# rev_o_v26.net
KiCad netlist of a schematic drawn in EAGLE
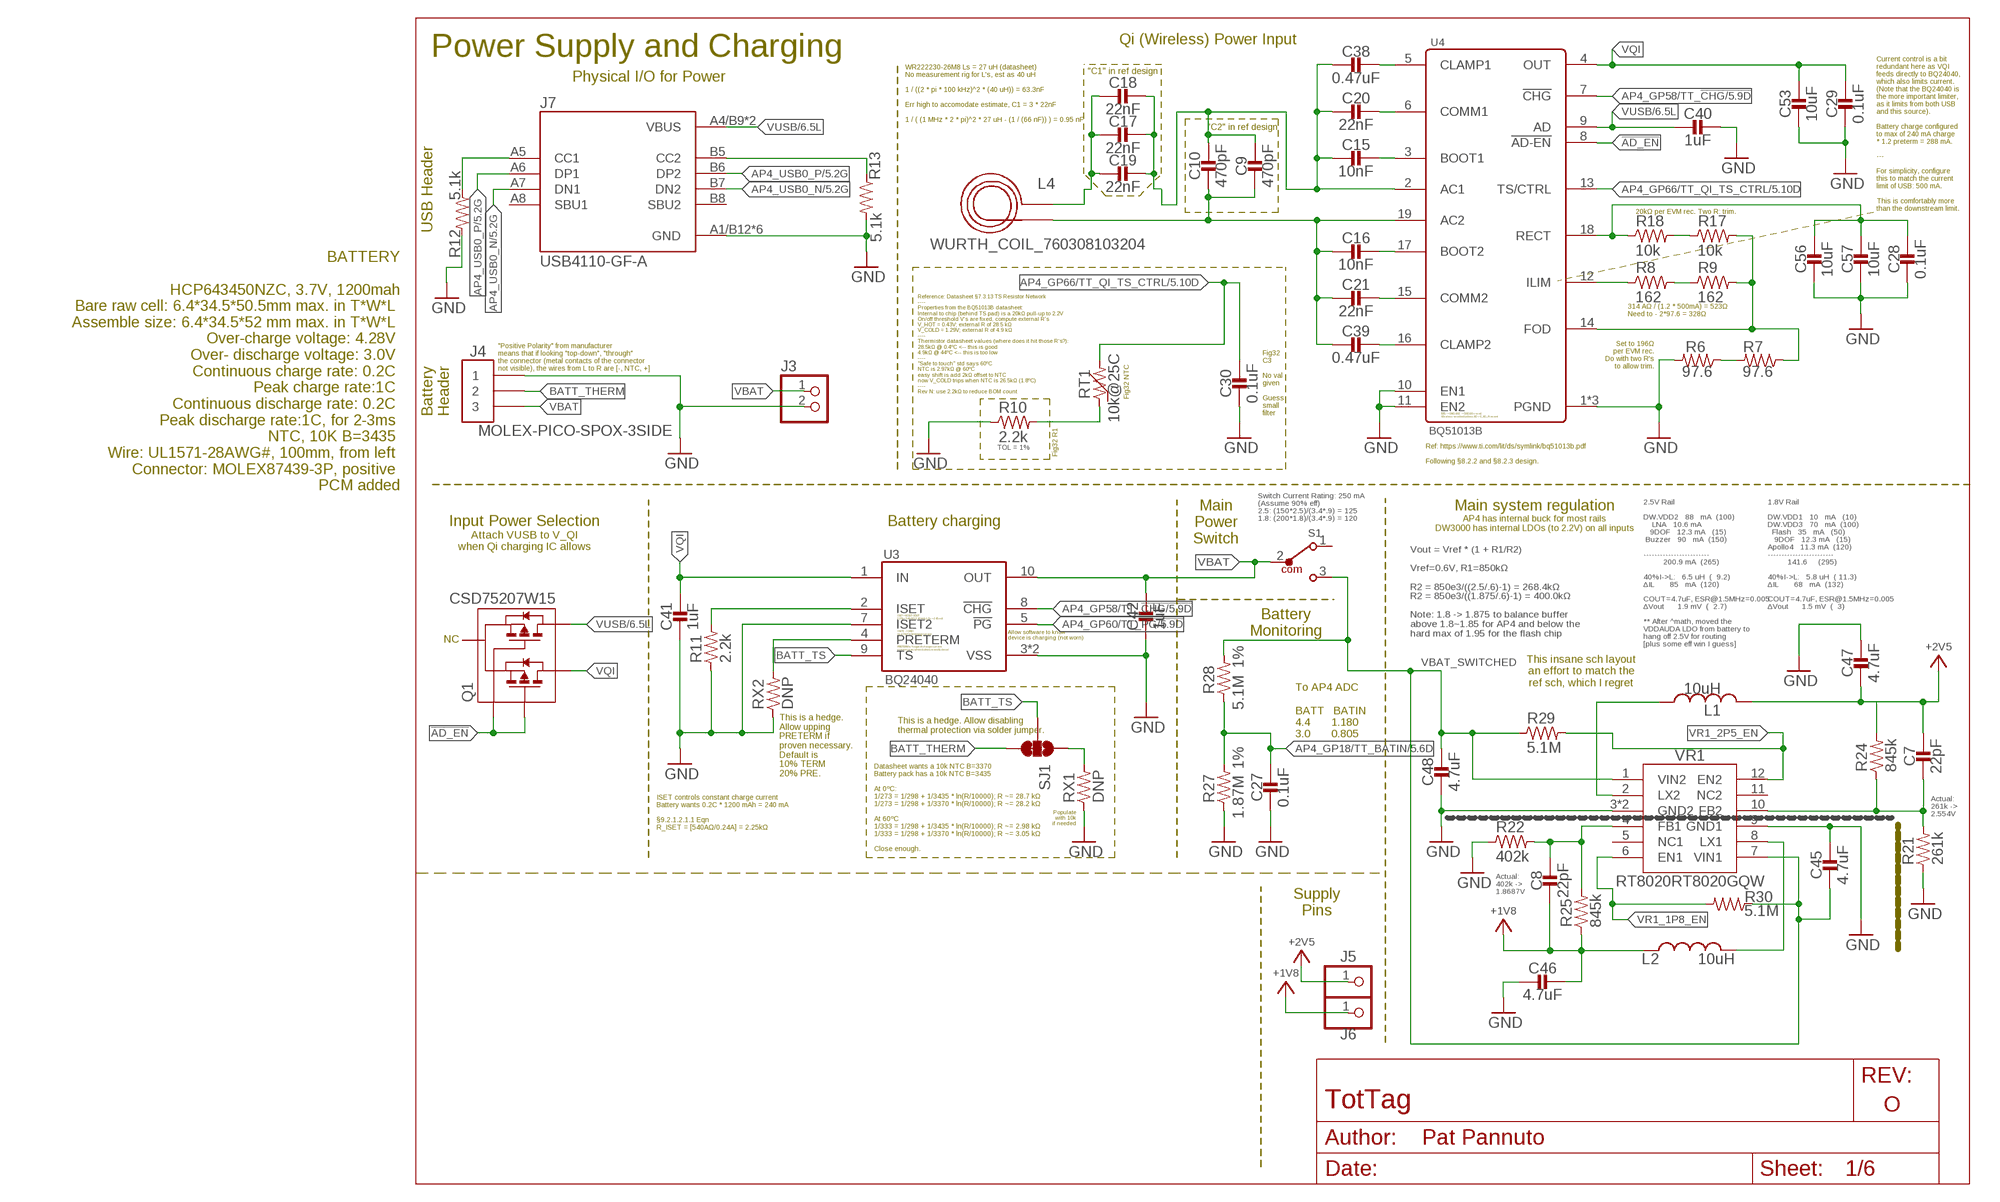
[diagram p0: schematic, sheet 1]
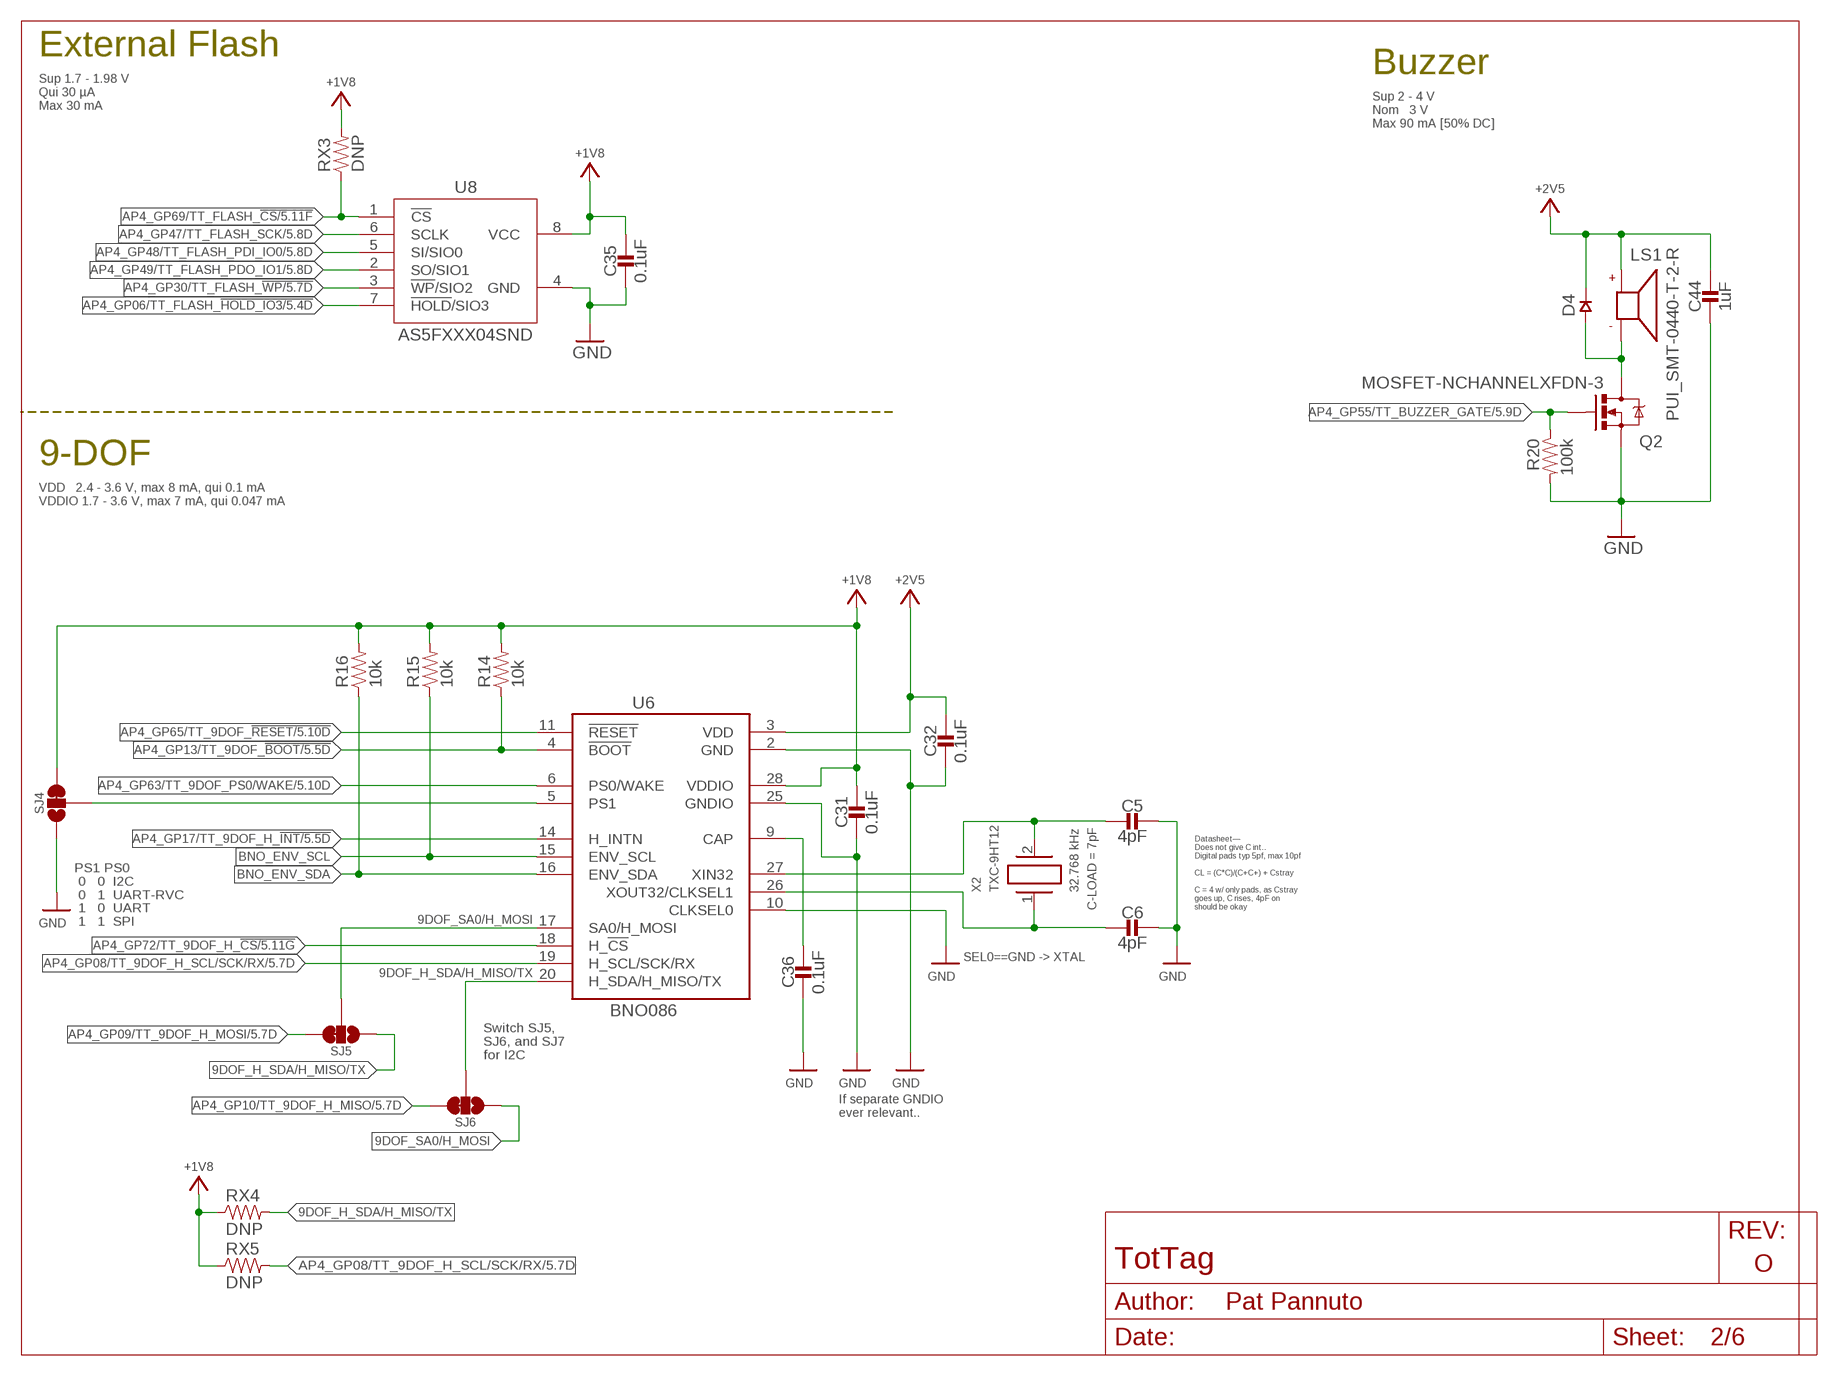
[diagram p1: schematic, sheet 2]
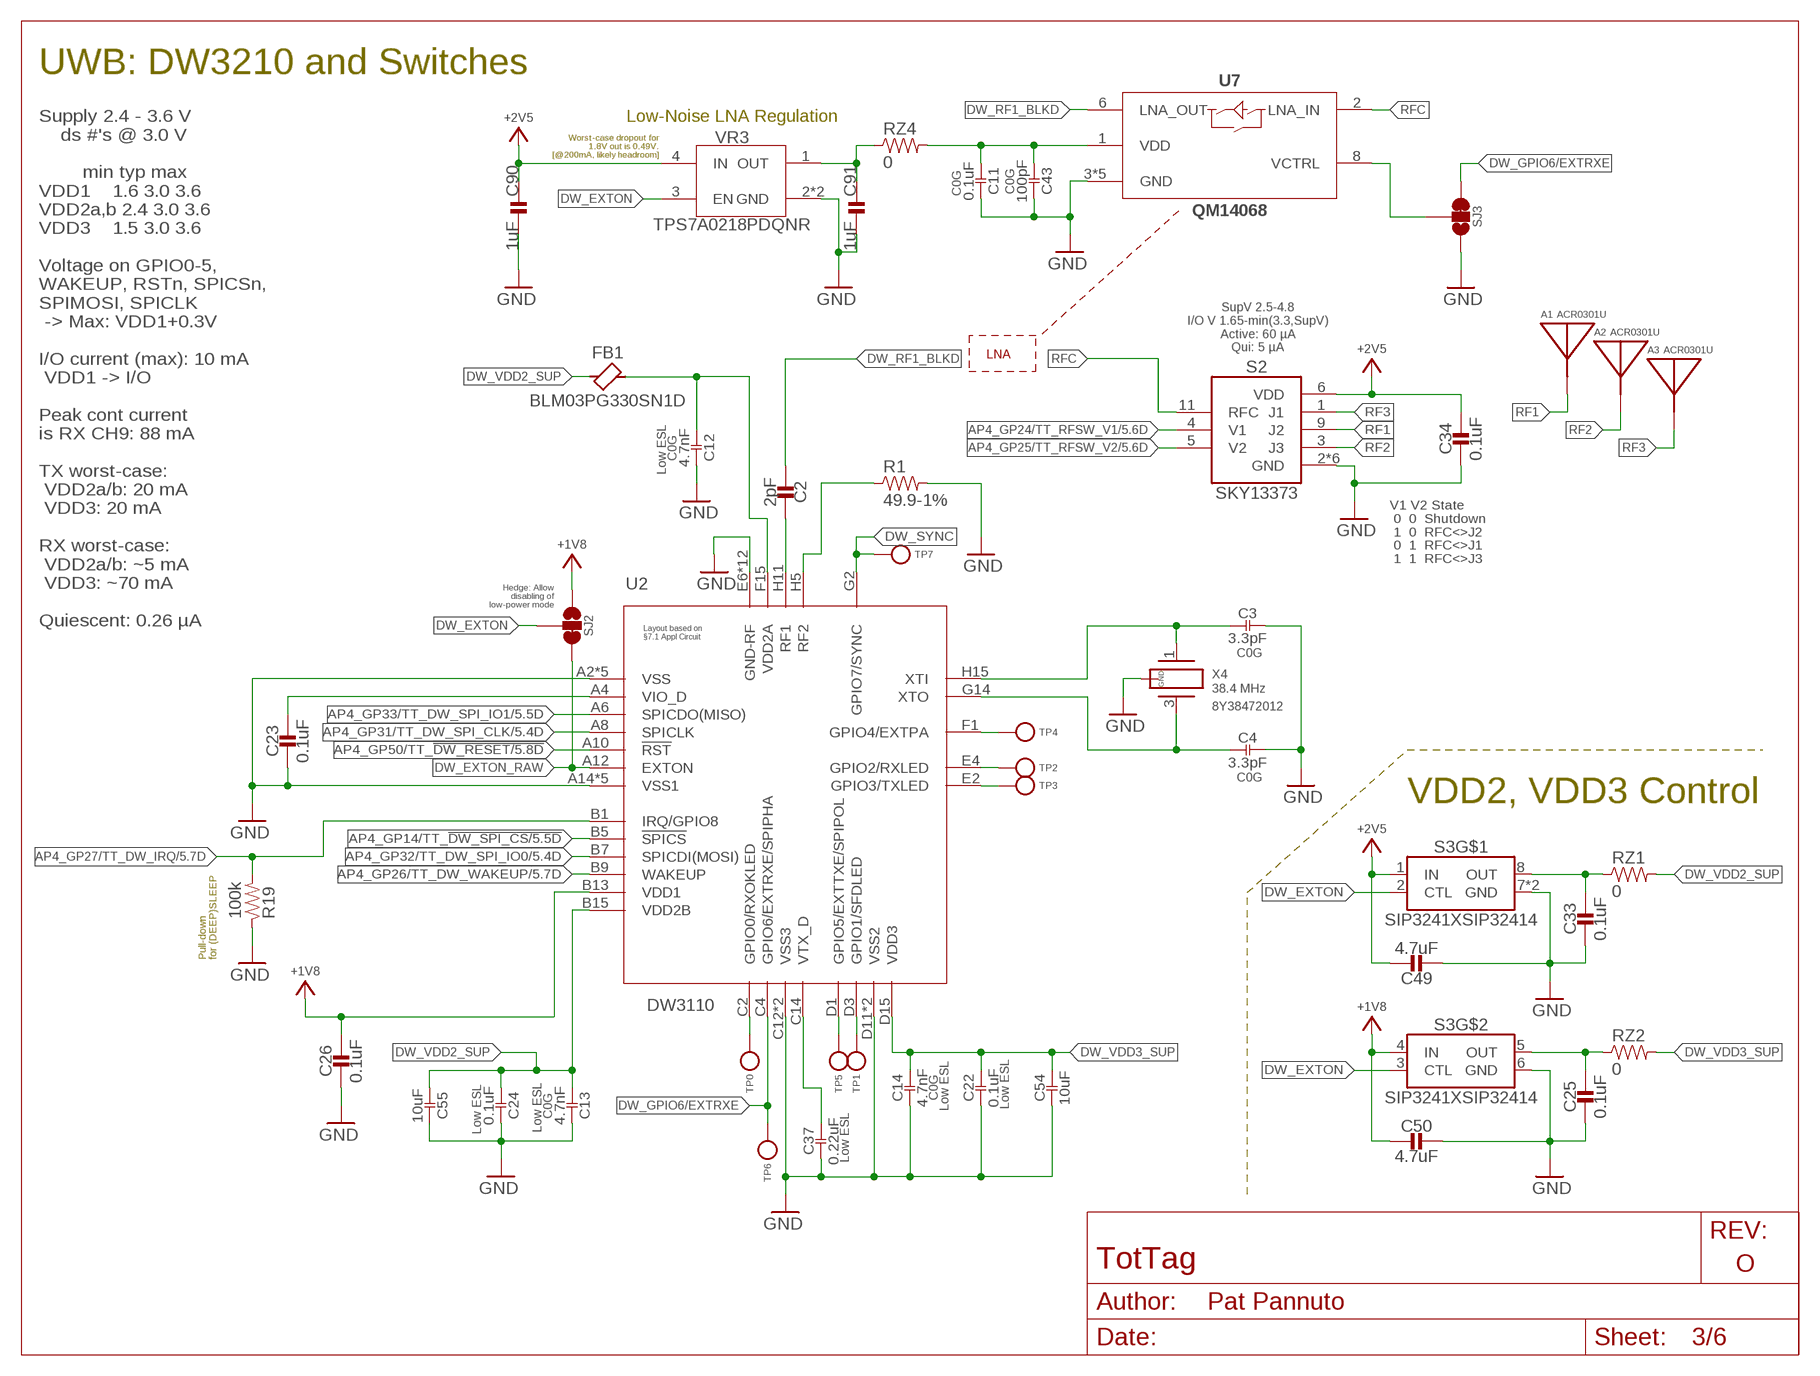
[diagram p2: schematic, sheet 3]
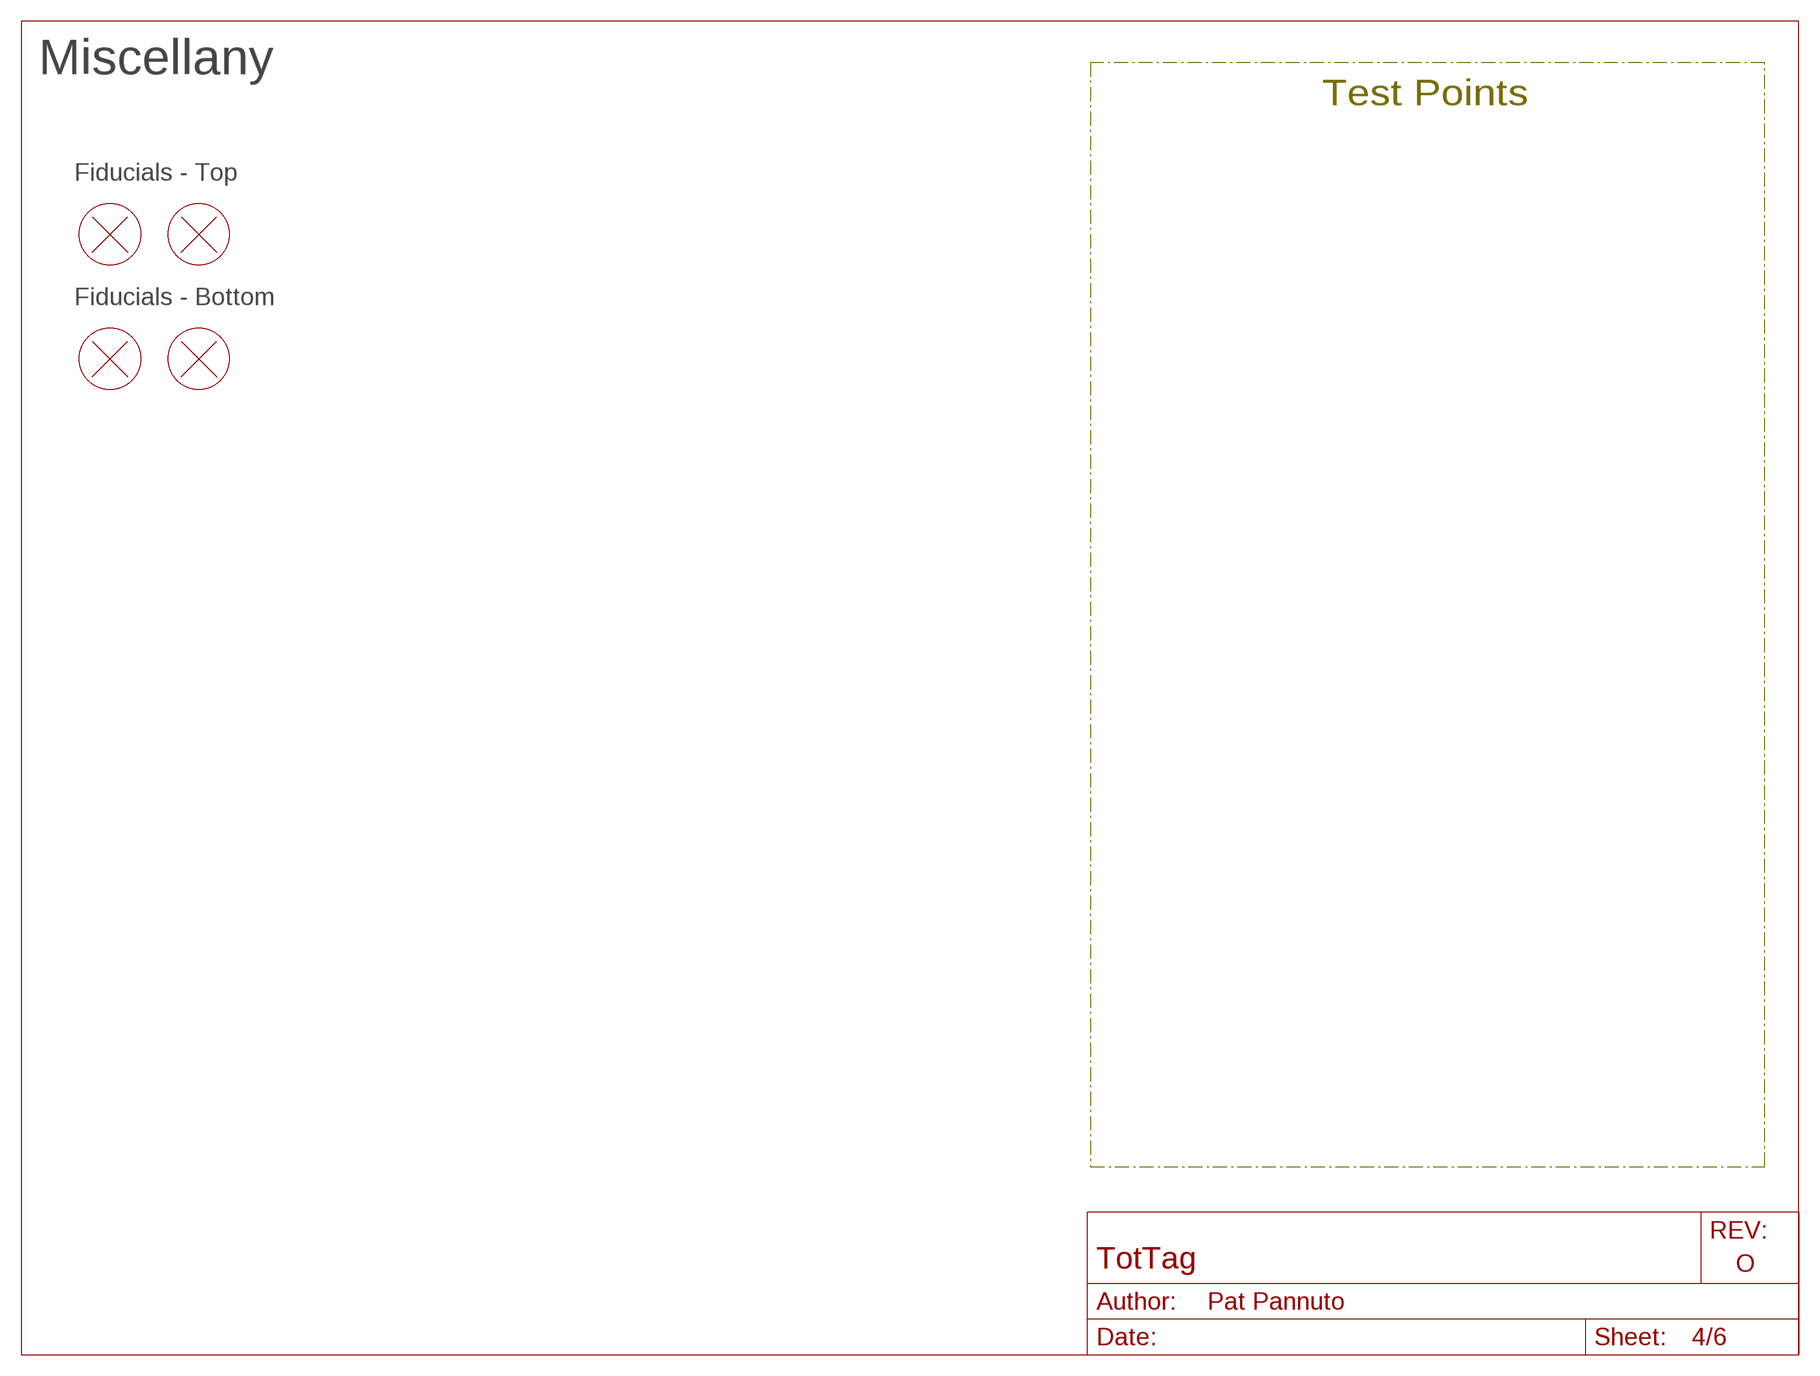
[diagram p3: schematic, sheet 4]
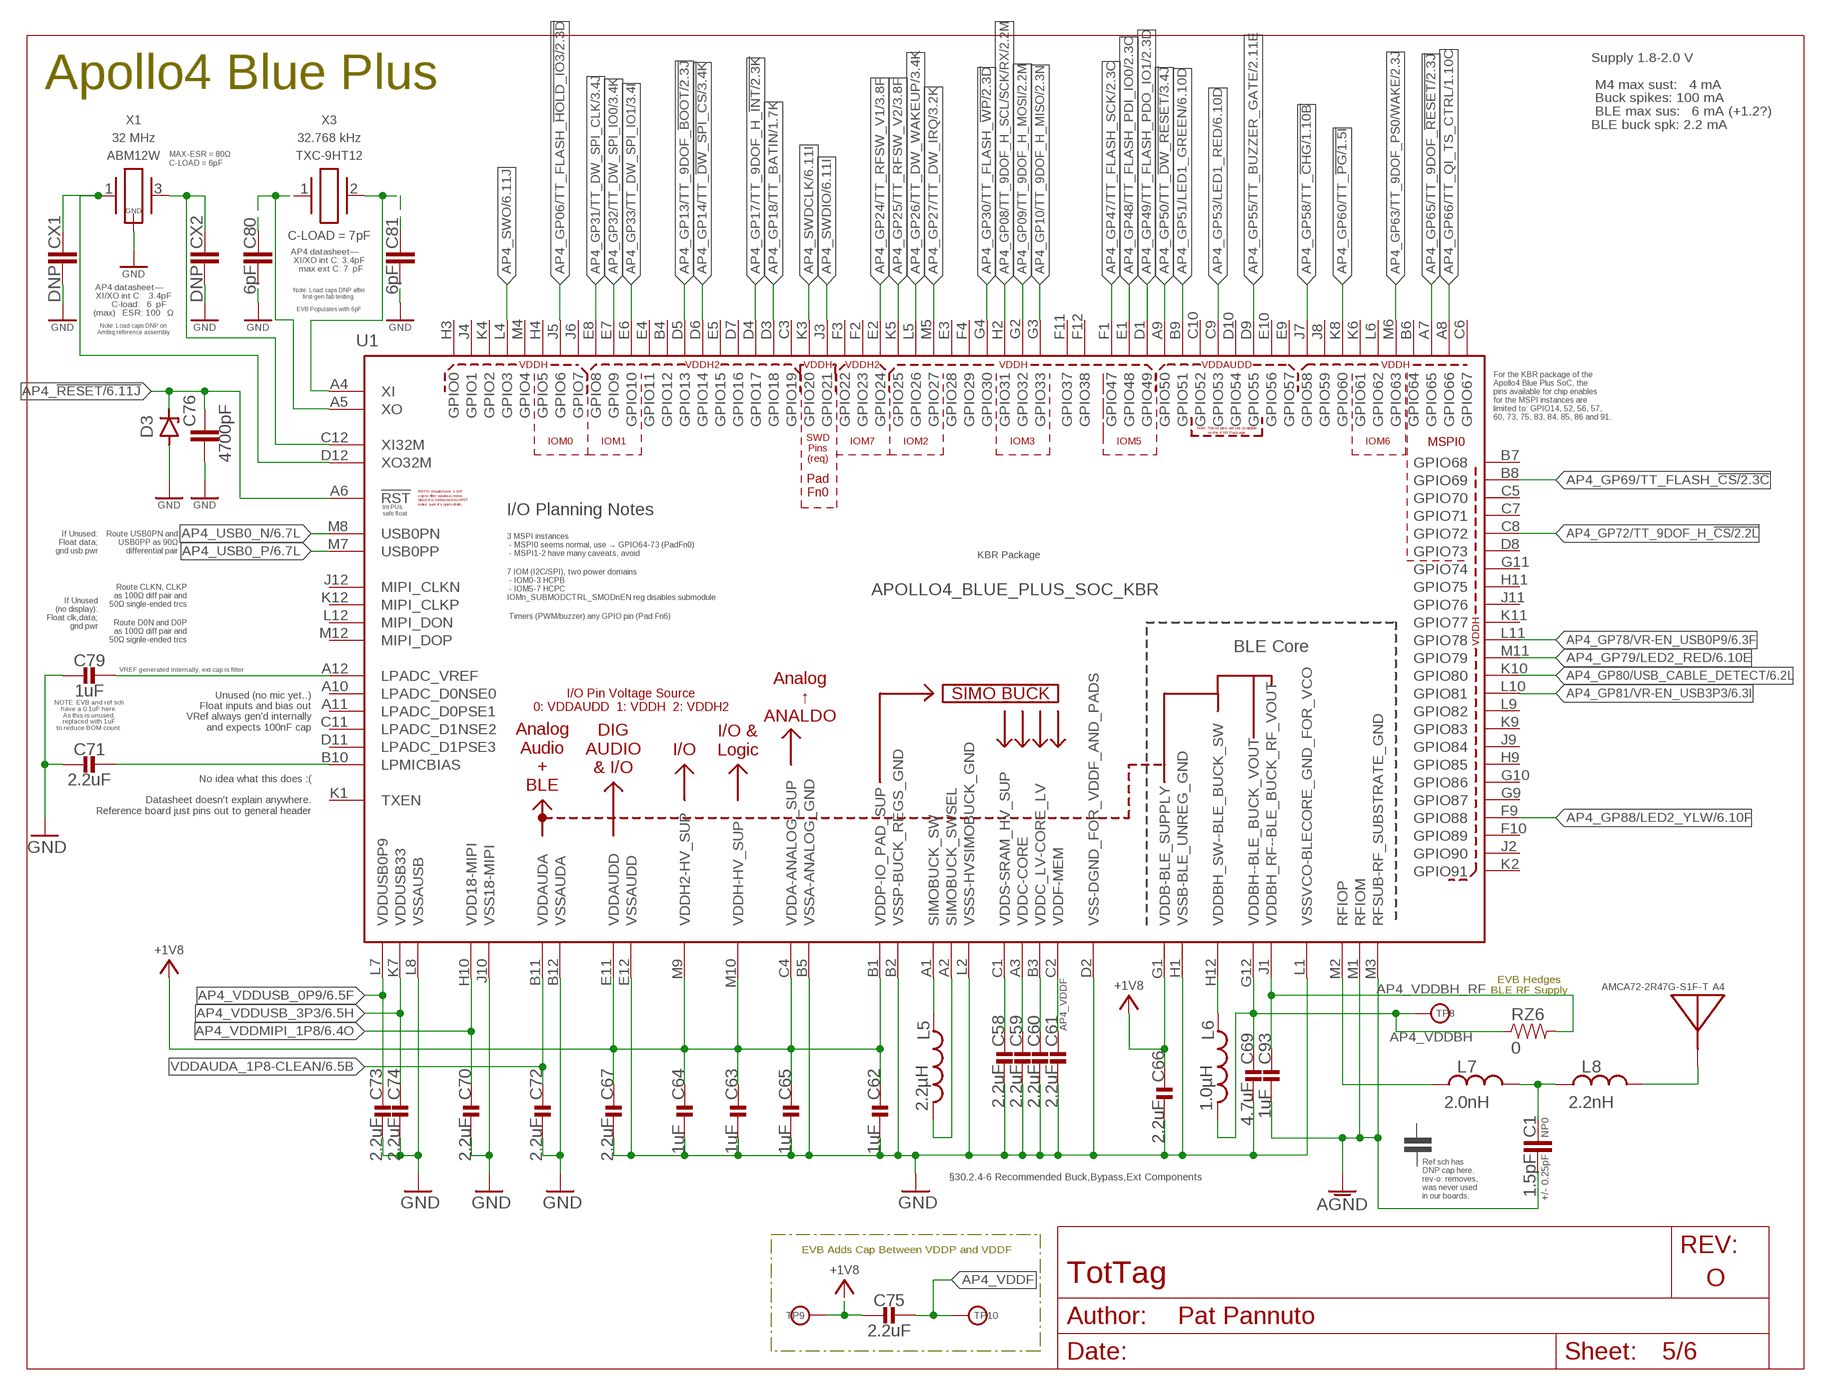
[diagram p4: schematic, sheet 5]
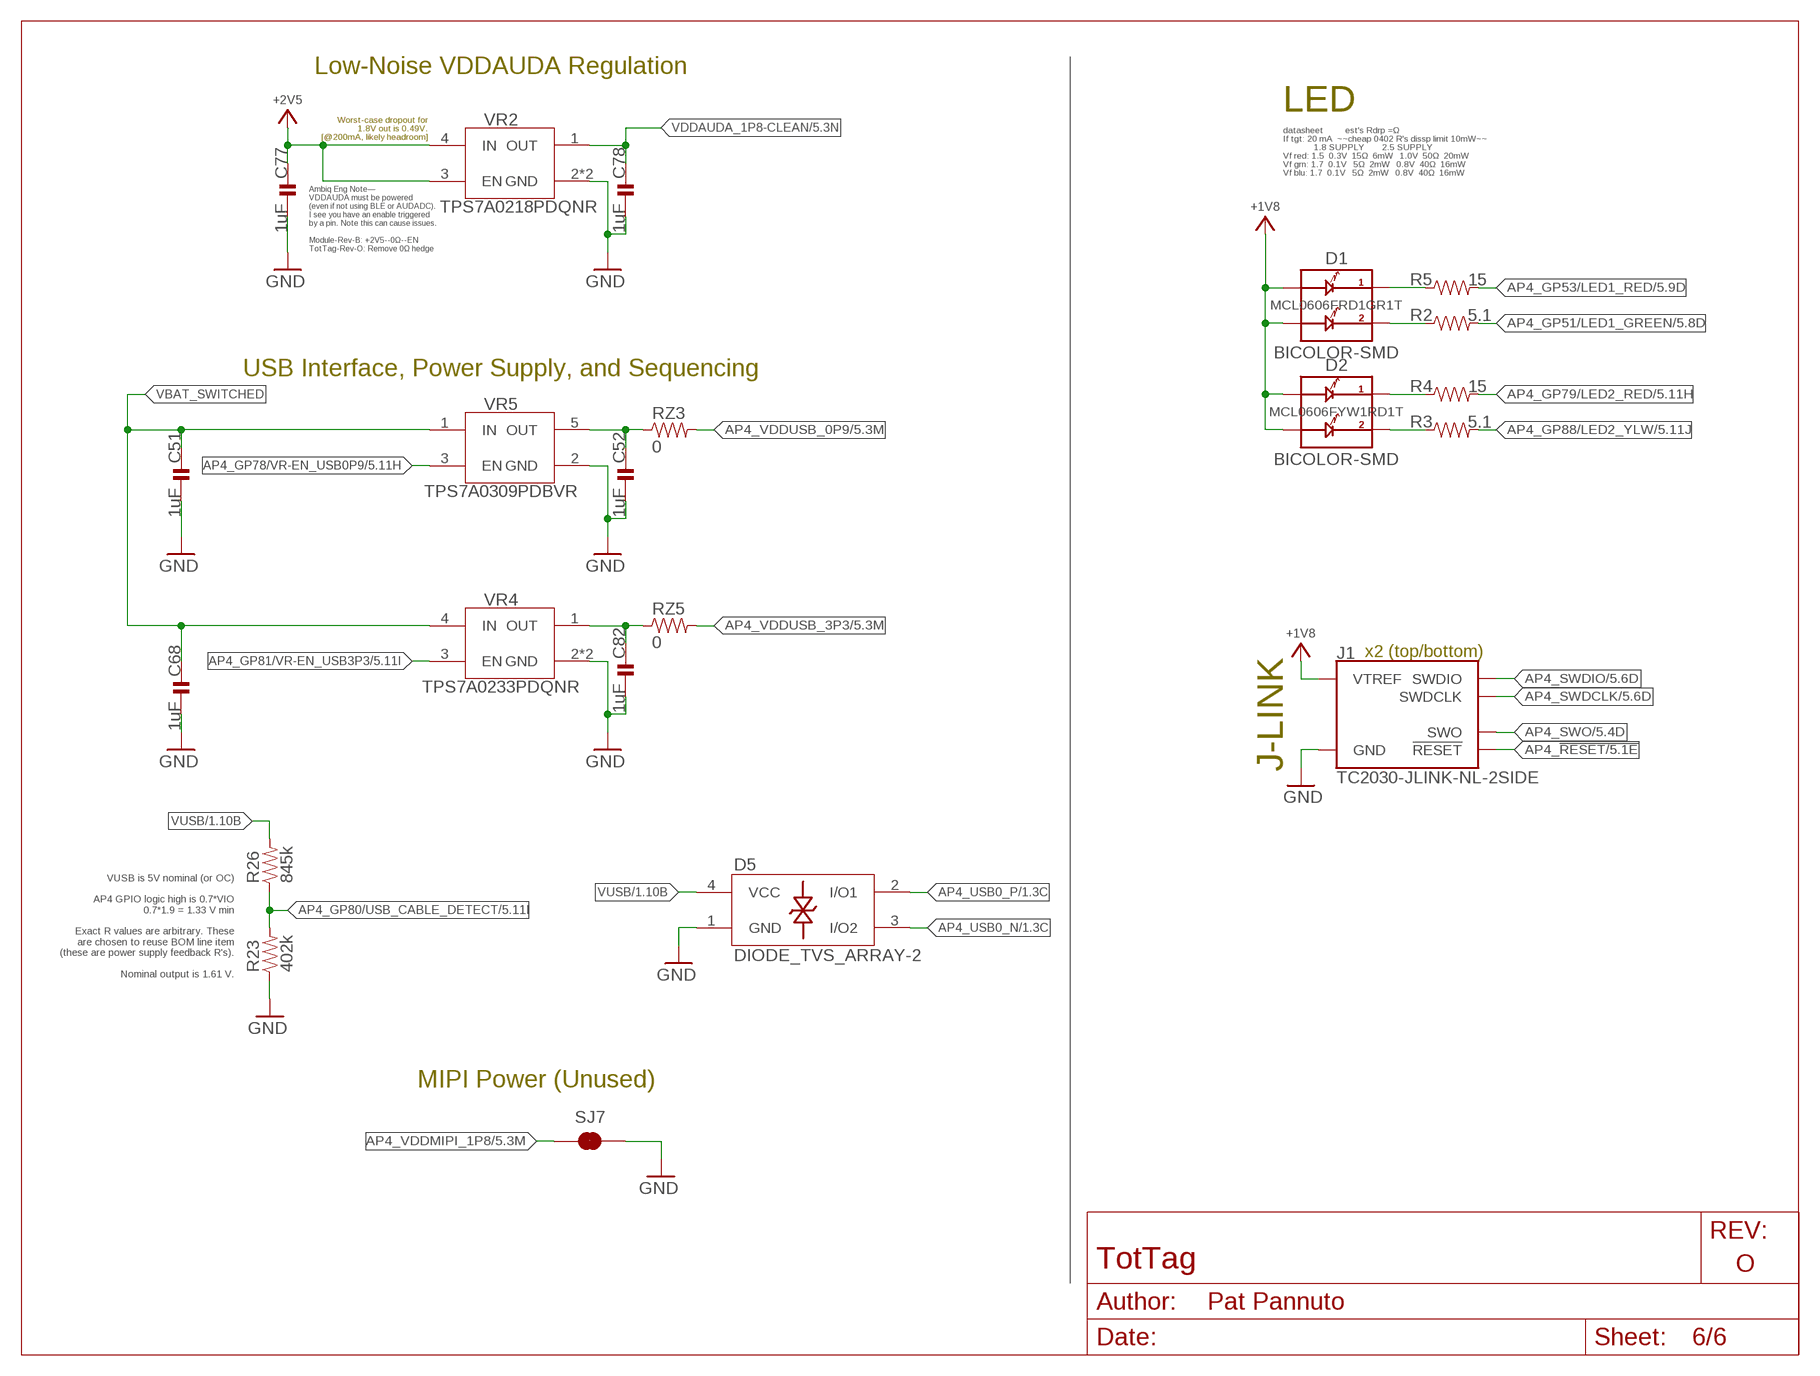
[diagram p5: schematic, sheet 6]

(export (version "E")
  (design (tool "Eeschema 10.0.6"))
  (components
    (comp (ref "C7")
      (value "22pF")
      (footprint "eagle-import:0201_CAP")
      (fields (field (name "MPN") "GRM0335C1H220FA01D"))
      (libsource (lib "eagle-import") (part "passives_20904581_CAPACITOR0201_CAP"))
    )
    (comp (ref "C8")
      (value "22pF")
      (footprint "eagle-import:0201_CAP")
      (fields (field (name "MPN") "GRM0335C1H220FA01D"))
      (libsource (lib "eagle-import") (part "passives_20904581_CAPACITOR0201_CAP"))
    )
    (comp (ref "C9")
      (value "470pF")
      (footprint "eagle-import:0402_CAP")
      (description "CAP CER 470PF 50V C0G/NP0 0402")
      (fields (field (name "MANUFACTURER") "Murata") (field (name "MPN") "GRM1555C1H471JA01J"))
      (libsource (lib "eagle-import") (part "passives_20904581_CAPACITOR0402_CAP"))
    )
    (comp (ref "C10")
      (value "470pF")
      (footprint "eagle-import:0402_CAP")
      (description "CAP CER 470PF 50V C0G/NP0 0402")
      (fields (field (name "MANUFACTURER") "Murata") (field (name "MPN") "GRM1555C1H471JA01J"))
      (libsource (lib "eagle-import") (part "passives_20904581_CAPACITOR0402_CAP"))
    )
    (comp (ref "C15")
      (value "10nF")
      (footprint "eagle-import:0402_CAP")
      (fields (field (name "MPN") "GRM155R71H103KA88J"))
      (libsource (lib "eagle-import") (part "passives_20904581_CAPACITOR0402_CAP"))
    )
    (comp (ref "C16")
      (value "10nF")
      (footprint "eagle-import:0402_CAP")
      (fields (field (name "MPN") "GRM155R71H103KA88J"))
      (libsource (lib "eagle-import") (part "passives_20904581_CAPACITOR0402_CAP"))
    )
    (comp (ref "C17")
      (value "22nF")
      (footprint "eagle-import:0402_CAP")
      (fields (field (name "MPN") "GRM155R71E223JA61D"))
      (libsource (lib "eagle-import") (part "passives_20904581_CAPACITOR0402_CAP"))
    )
    (comp (ref "C18")
      (value "22nF")
      (footprint "eagle-import:0402_CAP")
      (fields (field (name "MPN") "GRM155R71E223JA61D"))
      (libsource (lib "eagle-import") (part "passives_20904581_CAPACITOR0402_CAP"))
    )
    (comp (ref "C19")
      (value "22nF")
      (footprint "eagle-import:0402_CAP")
      (fields (field (name "MPN") "GRM155R71E223JA61D"))
      (libsource (lib "eagle-import") (part "passives_20904581_CAPACITOR0402_CAP"))
    )
    (comp (ref "C20")
      (value "22nF")
      (footprint "eagle-import:0402_CAP")
      (fields (field (name "MPN") "CC0402ZRY5V8BB223"))
      (libsource (lib "eagle-import") (part "passives_20904581_CAPACITOR0402_CAP"))
    )
    (comp (ref "C21")
      (value "22nF")
      (footprint "eagle-import:0402_CAP")
      (fields (field (name "MPN") "CC0402ZRY5V8BB223"))
      (libsource (lib "eagle-import") (part "passives_20904581_CAPACITOR0402_CAP"))
    )
    (comp (ref "C27")
      (value "0.1uF")
      (footprint "eagle-import:0402_CAP")
      (fields (field (name "MPN") "GRM155R71C104KA88J "))
      (libsource (lib "eagle-import") (part "CAPACITOR0402_CAP"))
    )
    (comp (ref "C28")
      (value "0.1uF")
      (footprint "eagle-import:0402_CAP")
      (fields (field (name "MPN") "GRM155R71C104KA88J "))
      (libsource (lib "eagle-import") (part "CAPACITOR0402_CAP"))
    )
    (comp (ref "C29")
      (value "0.1uF")
      (footprint "eagle-import:0402_CAP")
      (fields (field (name "MPN") "GRM155R71C104KA88J "))
      (libsource (lib "eagle-import") (part "CAPACITOR0402_CAP"))
    )
    (comp (ref "C30")
      (value "0.1uF")
      (footprint "eagle-import:0402_CAP")
      (fields (field (name "MPN") "GRM155R71C104KA88J "))
      (libsource (lib "eagle-import") (part "CAPACITOR0402_CAP"))
    )
    (comp (ref "C38")
      (value "0.47uF")
      (footprint "eagle-import:0402_CAP")
      (fields (field (name "MPN") "C1005X5R1E474K050BB"))
      (libsource (lib "eagle-import") (part "passives_20904581_CAPACITOR0402_CAP"))
    )
    (comp (ref "C39")
      (value "0.47uF")
      (footprint "eagle-import:0402_CAP")
      (fields (field (name "MPN") "C1005X5R1E474K050BB"))
      (libsource (lib "eagle-import") (part "passives_20904581_CAPACITOR0402_CAP"))
    )
    (comp (ref "C40")
      (value "1uF")
      (footprint "eagle-import:0402_CAP")
      (fields (field (name "MPN") "GRM155R70J105KA12J"))
      (libsource (lib "eagle-import") (part "CAPACITOR0402_CAP"))
    )
    (comp (ref "C41")
      (value "1uF")
      (footprint "eagle-import:0402_CAP")
      (fields (field (name "MPN") "GRM155R70J105KA12J"))
      (libsource (lib "eagle-import") (part "CAPACITOR0402_CAP"))
    )
    (comp (ref "C42")
      (value "1uF")
      (footprint "eagle-import:0402_CAP")
      (fields (field (name "MPN") "GRM155R70J105KA12J"))
      (libsource (lib "eagle-import") (part "CAPACITOR0402_CAP"))
    )
    (comp (ref "C45")
      (value "4.7uF")
      (footprint "eagle-import:0603_CAP")
      (fields (field (name "MPN") "C1608X7S1A475K080AC"))
      (libsource (lib "eagle-import") (part "passives_20904581_CAPACITOR0603_CAP"))
    )
    (comp (ref "C46")
      (value "4.7uF")
      (footprint "eagle-import:0603_CAP")
      (fields (field (name "MPN") "C1608X7S1A475K080AC"))
      (libsource (lib "eagle-import") (part "passives_20904581_CAPACITOR0603_CAP"))
    )
    (comp (ref "C47")
      (value "4.7uF")
      (footprint "eagle-import:0603_CAP")
      (fields (field (name "MPN") "C1608X7S1A475K080AC"))
      (libsource (lib "eagle-import") (part "passives_20904581_CAPACITOR0603_CAP"))
    )
    (comp (ref "C48")
      (value "4.7uF")
      (footprint "eagle-import:0603_CAP")
      (fields (field (name "MPN") "C1608X7S1A475K080AC"))
      (libsource (lib "eagle-import") (part "passives_20904581_CAPACITOR0603_CAP"))
    )
    (comp (ref "C53")
      (value "10uF")
      (footprint "eagle-import:0603_CAP")
      (fields (field (name "MPN") "CM105X5R106M25AT"))
      (libsource (lib "eagle-import") (part "passives_20904581_CAPACITOR0603_CAP"))
    )
    (comp (ref "C56")
      (value "10uF")
      (footprint "eagle-import:0603_CAP")
      (fields (field (name "MPN") "CM105X5R106M25AT"))
      (libsource (lib "eagle-import") (part "passives_20904581_CAPACITOR0603_CAP"))
    )
    (comp (ref "C57")
      (value "10uF")
      (footprint "eagle-import:0603_CAP")
      (fields (field (name "MPN") "CM105X5R106M25AT"))
      (libsource (lib "eagle-import") (part "passives_20904581_CAPACITOR0603_CAP"))
    )
    (comp (ref "J3")
      (value "PINHD-1X2")
      (footprint "eagle-import:1X02")
      (libsource (lib "eagle-import") (part "PINHD-1X2"))
    )
    (comp (ref "J4")
      (value "MOLEX-PICO-SPOX-3SIDE")
      (footprint "eagle-import:MOLEX-PICO-SPOX-3_SIDE")
      (libsource (lib "eagle-import") (part "MOLEX-PICO-SPOX-3SIDE"))
    )
    (comp (ref "J5")
      (value "PINHD-1X1")
      (footprint "eagle-import:1X01")
      (libsource (lib "eagle-import") (part "PINHD-1X1"))
    )
    (comp (ref "J6")
      (value "PINHD-1X1")
      (footprint "eagle-import:1X01")
      (libsource (lib "eagle-import") (part "PINHD-1X1"))
    )
    (comp (ref "J7")
      (value "USB4110-GF-A")
      (footprint "eagle-import:GCT_USB4110-GF-A")
      (fields (field (name "MF") "GCT"))
      (libsource (lib "eagle-import") (part "USB4110-GF-A"))
    )
    (comp (ref "L1")
      (value "10uH")
      (footprint "eagle-import:NRX3015")
      (fields (field (name "MANUFACTURER") "TAIYO YUDEN") (field (name "MPN") "NR3015T100M"))
      (libsource (lib "eagle-import") (part "INDUCTORNRX3015"))
    )
    (comp (ref "L2")
      (value "10uH")
      (footprint "eagle-import:NRX3015")
      (fields (field (name "MANUFACTURER") "TAIYO YUDEN") (field (name "MPN") "NR3015T100M"))
      (libsource (lib "eagle-import") (part "INDUCTORNRX3015"))
    )
    (comp (ref "L4")
      (value "WURTH_COIL_760308103204")
      (footprint "eagle-import:WURTH_COIL_760308103204")
      (fields (field (name "MANUFACTURER") "Würth Elektronik") (field (name "MPN") "760308103204"))
      (libsource (lib "eagle-import") (part "WURTH_COIL_760308103204"))
    )
    (comp (ref "Q1")
      (value "CSD75207W15")
      (footprint "eagle-import:DSBGA")
      (fields (field (name "MANUFACTURER") "TEXAS INSTRUMENTS"))
      (libsource (lib "eagle-import") (part "CSD75207W15"))
    )
    (comp (ref "R6")
      (value "97.6")
      (footprint "eagle-import:0402_RES")
      (fields (field (name "MPN") "RMCF0402FT97R6"))
      (libsource (lib "eagle-import") (part "passives_20904581_RESISTOR0402_RES"))
    )
    (comp (ref "R7")
      (value "97.6")
      (footprint "eagle-import:0402_RES")
      (fields (field (name "MPN") "RMCF0402FT97R6"))
      (libsource (lib "eagle-import") (part "passives_20904581_RESISTOR0402_RES"))
    )
    (comp (ref "R8")
      (value "162")
      (footprint "eagle-import:0402_RES")
      (fields (field (name "MPN") "RMCF0402FT162R"))
      (libsource (lib "eagle-import") (part "passives_20904581_RESISTOR0402_RES"))
    )
    (comp (ref "R9")
      (value "162")
      (footprint "eagle-import:0402_RES")
      (fields (field (name "MPN") "RMCF0402FT162R"))
      (libsource (lib "eagle-import") (part "passives_20904581_RESISTOR0402_RES"))
    )
    (comp (ref "R10")
      (value "2.2k")
      (footprint "eagle-import:0402_RES")
      (fields (field (name "MPN") "RC0402FR-072K2L") (field (name "TOL") "1%"))
      (libsource (lib "eagle-import") (part "RESISTOR0402_RES"))
    )
    (comp (ref "R11")
      (value "2.2k")
      (footprint "eagle-import:0402_RES")
      (fields (field (name "MPN") "RC0402FR-072K2L"))
      (libsource (lib "eagle-import") (part "passives_20904581_RESISTOR0402_RES"))
    )
    (comp (ref "R12")
      (value "5.1k")
      (footprint "eagle-import:0402_RES")
      (fields (field (name "MPN") "RMCF0402FT5K10"))
      (libsource (lib "eagle-import") (part "passives_20904581_RESISTOR0402_RES"))
    )
    (comp (ref "R13")
      (value "5.1k")
      (footprint "eagle-import:0402_RES")
      (fields (field (name "MPN") "RMCF0402FT5K10"))
      (libsource (lib "eagle-import") (part "passives_20904581_RESISTOR0402_RES"))
    )
    (comp (ref "R17")
      (value "10k")
      (footprint "eagle-import:0402_RES")
      (fields (field (name "MPN") "RC0402JR-0710KL"))
      (libsource (lib "eagle-import") (part "RESISTOR0402_RES"))
    )
    (comp (ref "R18")
      (value "10k")
      (footprint "eagle-import:0402_RES")
      (fields (field (name "MPN") "RC0402JR-0710KL"))
      (libsource (lib "eagle-import") (part "RESISTOR0402_RES"))
    )
    (comp (ref "R21")
      (value "261k")
      (footprint "eagle-import:0201_RES")
      (fields (field (name "MPN") "ERJ-1GNF2613C"))
      (libsource (lib "eagle-import") (part "passives_20904581_RESISTOR0201_RES"))
    )
    (comp (ref "R22")
      (value "402k")
      (footprint "eagle-import:0201_RES")
      (fields (field (name "MPN") "ERJ-1GNF4023C"))
      (libsource (lib "eagle-import") (part "passives_20904581_RESISTOR0201_RES"))
    )
    (comp (ref "R24")
      (value "845k")
      (footprint "eagle-import:0201_RES")
      (fields (field (name "MPN") "ERJ-1GNF8453C"))
      (libsource (lib "eagle-import") (part "passives_20904581_RESISTOR0201_RES"))
    )
    (comp (ref "R25")
      (value "845k")
      (footprint "eagle-import:0201_RES")
      (fields (field (name "MPN") "ERJ-1GNF8453C"))
      (libsource (lib "eagle-import") (part "passives_20904581_RESISTOR0201_RES"))
    )
    (comp (ref "R27")
      (value "1.87M")
      (footprint "eagle-import:0402_RES")
      (fields (field (name "MPN") "RMCF0402FT1M87") (field (name "TOLERANCE") "1%"))
      (libsource (lib "eagle-import") (part "RESISTOR0402_RES"))
    )
    (comp (ref "R28")
      (value "5.1M")
      (footprint "eagle-import:0402_RES")
      (fields (field (name "MPN") "RMCF0402FT5M10") (field (name "TOLERANCE") "1%"))
      (libsource (lib "eagle-import") (part "RESISTOR0402_RES"))
    )
    (comp (ref "R29")
      (value "5.1M")
      (footprint "eagle-import:0402_RES")
      (fields (field (name "MPN") "RMCF0402FT5M10"))
      (libsource (lib "eagle-import") (part "RESISTOR0402_RES"))
    )
    (comp (ref "R30")
      (value "5.1M")
      (footprint "eagle-import:0402_RES")
      (fields (field (name "MPN") "RMCF0402FT5M10"))
      (libsource (lib "eagle-import") (part "RESISTOR0402_RES"))
    )
    (comp (ref "RT1")
      (value "10k@25C")
      (footprint "eagle-import:0402_RES")
      (fields (field (name "MPN") "NCU15XH103F60RC"))
      (libsource (lib "eagle-import") (part "THERMISTOR0402"))
    )
    (comp (ref "RX1")
      (value "DNP")
      (footprint "eagle-import:0402_RES")
      (libsource (lib "eagle-import") (part "RESISTOR0402_RES"))
    )
    (comp (ref "RX2")
      (value "DNP")
      (footprint "eagle-import:0402_RES")
      (libsource (lib "eagle-import") (part "passives_20904581_RESISTOR0402_RES"))
    )
    (comp (ref "S1")
      (value "450404015514")
      (footprint "eagle-import:450404015514")
      (libsource (lib "eagle-import") (part "450404015514"))
    )
    (comp (ref "SJ1")
      (value "JUMPER-SMT_3_1-NC_TRACE_SILK")
      (footprint "eagle-import:SMT-JUMPER_3_1-NC_TRACE_SILK")
      (libsource (lib "eagle-import") (part "JUMPER-SMT_3_1-NC_TRACE_SILK"))
    )
    (comp (ref "U3")
      (value "BQ24040")
      (footprint "eagle-import:DSQ0010A")
      (fields (field (name "MPN") "BQ24040DSQR"))
      (libsource (lib "eagle-import") (part "BQ24040"))
    )
    (comp (ref "U4")
      (value "BQ51013B")
      (footprint "eagle-import:RHL0020A")
      (fields (field (name "MPN") "BQ51013BRHLR"))
      (libsource (lib "eagle-import") (part "BQ51013B"))
    )
    (comp (ref "VR1")
      (value "RT8020RT8020GQW")
      (footprint "eagle-import:SON45P300X300X80-13T160X250N")
      (fields (field (name "MANUFACTURER") "RichTek") (field (name "MPN") "RT8020GQW"))
      (libsource (lib "eagle-import") (part "RT8020RT8020GQW"))
    )
    (comp (ref "C5")
      (value "4pF")
      (footprint "eagle-import:0201_CAP")
      (fields (field (name "MANUFACTURER") "Murata") (field (name "MPN") "GRM0335C1H4R0BA01D"))
      (libsource (lib "eagle-import") (part "passives_20904581_CAPACITOR0201_CAP"))
    )
    (comp (ref "C6")
      (value "4pF")
      (footprint "eagle-import:0201_CAP")
      (fields (field (name "MANUFACTURER") "Murata") (field (name "MPN") "GRM0335C1H4R0BA01D"))
      (libsource (lib "eagle-import") (part "passives_20904581_CAPACITOR0201_CAP"))
    )
    (comp (ref "C31")
      (value "0.1uF")
      (footprint "eagle-import:0402_CAP")
      (fields (field (name "MPN") "CL05A104KP5NNNC"))
      (libsource (lib "eagle-import") (part "passives_20904581_CAPACITOR0402_CAP"))
    )
    (comp (ref "C32")
      (value "0.1uF")
      (footprint "eagle-import:0402_CAP")
      (fields (field (name "MPN") "CL05A104KP5NNNC"))
      (libsource (lib "eagle-import") (part "passives_20904581_CAPACITOR0402_CAP"))
    )
    (comp (ref "C35")
      (value "0.1uF")
      (footprint "eagle-import:0402_CAP")
      (fields (field (name "MPN") "CL05A104KP5NNNC"))
      (libsource (lib "eagle-import") (part "passives_20904581_CAPACITOR0402_CAP"))
    )
    (comp (ref "C36")
      (value "0.1uF")
      (footprint "eagle-import:0402_CAP")
      (fields (field (name "MPN") "CL05A104KP5NNNC"))
      (libsource (lib "eagle-import") (part "CAPACITOR0402_CAP"))
    )
    (comp (ref "C44")
      (value "1uF")
      (footprint "eagle-import:0402_CAP")
      (fields (field (name "MPN") "GRM155R70J105KA12J"))
      (libsource (lib "eagle-import") (part "CAPACITOR0402_CAP"))
    )
    (comp (ref "D4")
      (value "DIODE0402")
      (footprint "eagle-import:0402_DIODE")
      (fields (field (name "MPN") "CDSQR400B-HF"))
      (libsource (lib "eagle-import") (part "DIODE0402"))
    )
    (comp (ref "LS1")
      (value "PUI_SMT-0440-T-2-R")
      (footprint "eagle-import:SMT-0440-T-2-R")
      (fields (field (name "MPN") "SMT-0440-T-2-R"))
      (libsource (lib "eagle-import") (part "PUI_SMT-0440-T-2-R"))
    )
    (comp (ref "Q2")
      (value "MOSFET-NCHANNELXFDN-3")
      (footprint "eagle-import:XFDFN-3")
      (libsource (lib "eagle-import") (part "MOSFET-NCHANNELXFDN-3"))
    )
    (comp (ref "R14")
      (value "10k")
      (footprint "eagle-import:0402_RES")
      (fields (field (name "MPN") "RC0402JR-0710KL"))
      (libsource (lib "eagle-import") (part "RESISTOR0402_RES"))
    )
    (comp (ref "R15")
      (value "10k")
      (footprint "eagle-import:0402_RES")
      (fields (field (name "MPN") "RC0402JR-0710KL"))
      (libsource (lib "eagle-import") (part "RESISTOR0402_RES"))
    )
    (comp (ref "R16")
      (value "10k")
      (footprint "eagle-import:0402_RES")
      (fields (field (name "MPN") "RC0402JR-0710KL"))
      (libsource (lib "eagle-import") (part "RESISTOR0402_RES"))
    )
    (comp (ref "R20")
      (value "100k")
      (footprint "eagle-import:0402_RES")
      (fields (field (name "MPN") "RT0402BRE07100KL"))
      (libsource (lib "eagle-import") (part "RESISTOR0402_RES"))
    )
    (comp (ref "RX3")
      (value "DNP")
      (footprint "eagle-import:0603-RES")
      (libsource (lib "eagle-import") (part "passives_20904581_RESISTOR0603_RES"))
    )
    (comp (ref "RX4")
      (value "DNP")
      (footprint "eagle-import:0603-RES")
      (libsource (lib "eagle-import") (part "passives_20904581_RESISTOR0603_RES"))
    )
    (comp (ref "RX5")
      (value "DNP")
      (footprint "eagle-import:0603-RES")
      (libsource (lib "eagle-import") (part "passives_20904581_RESISTOR0603_RES"))
    )
    (comp (ref "SJ4")
      (value "JUMPER-SMT_3_1-NC_TRACE_SILK")
      (footprint "eagle-import:SMT-JUMPER_3_1-NC_TRACE_SILK")
      (libsource (lib "eagle-import") (part "JUMPER-SMT_3_1-NC_TRACE_SILK"))
    )
    (comp (ref "SJ5")
      (value "JUMPER-SMT_3_1-NC_TRACE_SILK")
      (footprint "eagle-import:SMT-JUMPER_3_1-NC_TRACE_SILK")
      (libsource (lib "eagle-import") (part "JUMPER-SMT_3_1-NC_TRACE_SILK"))
    )
    (comp (ref "SJ6")
      (value "JUMPER-SMT_3_1-NC_TRACE_SILK")
      (footprint "eagle-import:SMT-JUMPER_3_1-NC_TRACE_SILK")
      (libsource (lib "eagle-import") (part "JUMPER-SMT_3_1-NC_TRACE_SILK"))
    )
    (comp (ref "U6")
      (value "BNO086")
      (footprint "eagle-import:LGA28R0P510X4_5P2X3P8X1")
      (fields (field (name "MANUFACTURER") "CEVA Technologies, Inc."))
      (libsource (lib "eagle-import") (part "BNO086"))
    )
    (comp (ref "U8")
      (value "AS5FXXX04SND")
      (footprint "eagle-import:AS5FXXXXXXXX-XXLXN")
      (fields (field (name "MANUFACTURER") "Alliance Memory") (field (name "MPN") "AS5F18G04SND-10LIN"))
      (libsource (lib "eagle-import") (part "AS5FXXX04SND"))
    )
    (comp (ref "X2")
      (value "TXC-9HT12")
      (footprint "eagle-import:TXC-9HT12")
      (fields
        (field (name "C-LOAD") "7pF")
        (field (name "FREQUENCY") "32.768 kHz")
        (field (name "MANUFACTURER") "TXC Corp")
        (field (name "MPN") "9HT12-32.768KDZY-T")
      )
      (libsource (lib "eagle-import") (part "TXC-9HT12"))
    )
    (comp (ref "A1")
      (value "ACR0301U")
      (footprint "eagle-import:ACR0301U")
      (fields (field (name "MANUFACTURER") "Abracon"))
      (libsource (lib "eagle-import") (part "ACR0301U"))
    )
    (comp (ref "A2")
      (value "ACR0301U")
      (footprint "eagle-import:ACR0301U")
      (fields (field (name "MANUFACTURER") "Abracon"))
      (libsource (lib "eagle-import") (part "ACR0301U"))
    )
    (comp (ref "A3")
      (value "ACR0301U")
      (footprint "eagle-import:ACR0301U")
      (fields (field (name "MANUFACTURER") "Abracon"))
      (libsource (lib "eagle-import") (part "ACR0301U"))
    )
    (comp (ref "C2")
      (value "2pF")
      (footprint "eagle-import:0201_CAP")
      (fields (field (name "MPN") "CBR02C209A5GAC"))
      (libsource (lib "eagle-import") (part "CAPACITOR0201_CAP"))
    )
    (comp (ref "C3")
      (value "3.3pF")
      (footprint "eagle-import:SMD_2012M-0805US-C")
      (fields
        (field (name "EIA") "C0G")
        (field (name "MANUFACTURER") "KYOCERA AVX")
        (field (name "MPN") "600F3R3BT250XT")
      )
      (libsource (lib "eagle-import") (part "C0805US"))
    )
    (comp (ref "C4")
      (value "3.3pF")
      (footprint "eagle-import:SMD_2012M-0805US-C")
      (fields
        (field (name "EIA") "C0G")
        (field (name "MANUFACTURER") "KYOCERA AVX")
        (field (name "MPN") "600F3R3BT250XT")
      )
      (libsource (lib "eagle-import") (part "C0805US"))
    )
    (comp (ref "C11")
      (value "0.1uF")
      (footprint "eagle-import:SMD_3216M-1206US-C")
      (fields (field (name "EIA") "C0G") (field (name "MPN") "GRM31C5C1H104JA01L"))
      (libsource (lib "eagle-import") (part "C1206US"))
    )
    (comp (ref "C12")
      (value "4.7nF")
      (footprint "eagle-import:SMD_1608M-0603US-C")
      (fields
        (field (name "EIA") "C0G")
        (field (name "FEATURES") "Low ESL")
        (field (name "MANUFACTURER") "KEMET")
        (field (name "MPN") "C0603C472J5GACTU")
      )
      (libsource (lib "eagle-import") (part "C0603US"))
    )
    (comp (ref "C13")
      (value "4.7nF")
      (footprint "eagle-import:SMD_1608M-0603US-C")
      (fields
        (field (name "EIA") "C0G")
        (field (name "FEATURES") "Low ESL")
        (field (name "MANUFACTURER") "KEMET")
        (field (name "MPN") "C0603C472J5GACTU")
      )
      (libsource (lib "eagle-import") (part "C0603US"))
    )
    (comp (ref "C14")
      (value "4.7nF")
      (footprint "eagle-import:SMD_1608M-0603US-C")
      (fields
        (field (name "EIA") "C0G")
        (field (name "FEATURES") "Low ESL")
        (field (name "MANUFACTURER") "KEMET")
        (field (name "MPN") "C0603C472J5GACTU")
      )
      (libsource (lib "eagle-import") (part "C0603US"))
    )
    (comp (ref "C22")
      (value "0.1uF")
      (footprint "eagle-import:SMD_1608M-0603US-C")
      (fields (field (name "FEATURES") "Low ESL") (field (name "MPN") "C1608X7R1H104K080AA"))
      (libsource (lib "eagle-import") (part "C0603US"))
    )
    (comp (ref "C23")
      (value "0.1uF")
      (footprint "eagle-import:0402_CAP")
      (fields (field (name "MPN") "CL05A104KP5NNNC"))
      (libsource (lib "eagle-import") (part "passives_20904581_CAPACITOR0402_CAP"))
    )
    (comp (ref "C24")
      (value "0.1uF")
      (footprint "eagle-import:SMD_1608M-0603US-C")
      (fields (field (name "FEATURES") "Low ESL") (field (name "MPN") "C1608X7R1H104K080AA"))
      (libsource (lib "eagle-import") (part "C0603US"))
    )
    (comp (ref "C25")
      (value "0.1uF")
      (footprint "eagle-import:0402_CAP")
      (fields (field (name "MPN") "CL05A104KP5NNNC"))
      (libsource (lib "eagle-import") (part "passives_20904581_CAPACITOR0402_CAP"))
    )
    (comp (ref "C26")
      (value "0.1uF")
      (footprint "eagle-import:0402_CAP")
      (fields (field (name "MPN") "CL05A104KP5NNNC"))
      (libsource (lib "eagle-import") (part "passives_20904581_CAPACITOR0402_CAP"))
    )
    (comp (ref "C33")
      (value "0.1uF")
      (footprint "eagle-import:0402_CAP")
      (fields (field (name "MPN") "CL05A104KP5NNNC"))
      (libsource (lib "eagle-import") (part "passives_20904581_CAPACITOR0402_CAP"))
    )
    (comp (ref "C34")
      (value "0.1uF")
      (footprint "eagle-import:0402_CAP")
      (fields (field (name "MPN") "CL05A104KP5NNNC"))
      (libsource (lib "eagle-import") (part "passives_20904581_CAPACITOR0402_CAP"))
    )
    (comp (ref "C37")
      (value "0.22uF")
      (footprint "eagle-import:SMD_1608M-0603US-C")
      (fields (field (name "FEATURES") "Low ESL") (field (name "MPN") "C1608X7R1H224K080AB"))
      (libsource (lib "eagle-import") (part "C0603US"))
    )
    (comp (ref "C43")
      (value "100pF")
      (footprint "eagle-import:SMD_1005M-0402US-C")
      (fields (field (name "EIA") "C0G") (field (name "MPN") "C0402C101J3GACTU"))
      (libsource (lib "eagle-import") (part "C0402US"))
    )
    (comp (ref "C49")
      (value "4.7uF")
      (footprint "eagle-import:0603_CAP")
      (fields (field (name "MPN") "C1608X7S1A475K080AC"))
      (libsource (lib "eagle-import") (part "passives_20904581_CAPACITOR0603_CAP"))
    )
    (comp (ref "C50")
      (value "4.7uF")
      (footprint "eagle-import:0603_CAP")
      (fields (field (name "MPN") "C1608X7S1A475K080AC"))
      (libsource (lib "eagle-import") (part "passives_20904581_CAPACITOR0603_CAP"))
    )
    (comp (ref "C54")
      (value "10uF")
      (footprint "eagle-import:SMD_1608M-0603US-C")
      (fields (field (name "MPN") "CM105X5R106M25AT"))
      (libsource (lib "eagle-import") (part "C0603US"))
    )
    (comp (ref "C55")
      (value "10uF")
      (footprint "eagle-import:SMD_1608M-0603US-C")
      (fields (field (name "MPN") "CM105X5R106M25AT"))
      (libsource (lib "eagle-import") (part "C0603US"))
    )
    (comp (ref "C90")
      (value "1uF")
      (footprint "eagle-import:0201_CAP")
      (fields (field (name "MANUFACTURER") "Murata") (field (name "MPN") "GRM033R61A105ME44D"))
      (libsource (lib "eagle-import") (part "passives_20904581_CAPACITOR0201_CAP"))
    )
    (comp (ref "C91")
      (value "1uF")
      (footprint "eagle-import:0201_CAP")
      (fields (field (name "MANUFACTURER") "Murata") (field (name "MPN") "GRM033R61A105ME44D"))
      (libsource (lib "eagle-import") (part "passives_20904581_CAPACITOR0201_CAP"))
    )
    (comp (ref "FB1")
      (value "BLM03PG330SN1D")
      (footprint "eagle-import:0201_FB")
      (fields (field (name "MANUFACTURER") "Murata"))
      (libsource (lib "eagle-import") (part "FERRITE_BEAD0201"))
    )
    (comp (ref "R1")
      (value "49.9-1%")
      (footprint "eagle-import:0201_RES")
      (fields (field (name "MPN") "ERJ-1GNF49R9C"))
      (libsource (lib "eagle-import") (part "passives_20904581_RESISTOR0201_RES"))
    )
    (comp (ref "R19")
      (value "100k")
      (footprint "eagle-import:0402_RES")
      (fields (field (name "MPN") "RT0402BRE07100KL"))
      (libsource (lib "eagle-import") (part "RESISTOR0402_RES"))
    )
    (comp (ref "RZ1")
      (value "0")
      (footprint "eagle-import:0603-RES")
      (fields (field (name "MPN") "RMCF0603ZT0R00"))
      (libsource (lib "eagle-import") (part "passives_20904581_RESISTOR0603_RES"))
    )
    (comp (ref "RZ2")
      (value "0")
      (footprint "eagle-import:0603-RES")
      (fields (field (name "MPN") "RMCF0603ZT0R00"))
      (libsource (lib "eagle-import") (part "passives_20904581_RESISTOR0603_RES"))
    )
    (comp (ref "RZ4")
      (value "0")
      (footprint "eagle-import:0402_RES")
      (fields (field (name "MPN") "RMCF0402ZT0R00"))
      (libsource (lib "eagle-import") (part "passives_20904581_RESISTOR0402_RES"))
    )
    (comp (ref "S2")
      (value "SKY13373")
      (footprint "eagle-import:SKY13373")
      (fields (field (name "MANUFACTURER") "Skyworks") (field (name "MPN") "SKY13373-460LF"))
      (libsource (lib "eagle-import") (part "SKY13373"))
    )
    (comp (ref "S3")
      (value "SIP3241XSIP32414")
      (footprint "eagle-import:TDFN2X2X0P6-8")
      (fields (field (name "MANUFACTURER") "Vishay") (field (name "MPN") "SIP32414DNP-T1-GE4"))
      (libsource (lib "eagle-import") (part "SIP3241XSIP32414"))
    )
    (comp (ref "SJ2")
      (value "JUMPER-SMT_3_1-NC_TRACE_SILK")
      (footprint "eagle-import:SMT-JUMPER_3_1-NC_TRACE_SILK")
      (libsource (lib "eagle-import") (part "JUMPER-SMT_3_1-NC_TRACE_SILK"))
    )
    (comp (ref "SJ3")
      (value "JUMPER-SMT_3_1-NC_TRACE_SILK")
      (footprint "eagle-import:SMT-JUMPER_3_1-NC_TRACE_SILK")
      (libsource (lib "eagle-import") (part "JUMPER-SMT_3_1-NC_TRACE_SILK"))
    )
    (comp (ref "TP0")
      (value "TEST-POINT")
      (footprint "eagle-import:PAD.03X.03")
      (libsource (lib "eagle-import") (part "TEST-POINT"))
    )
    (comp (ref "TP1")
      (value "TEST-POINT")
      (footprint "eagle-import:PAD.03X.03")
      (libsource (lib "eagle-import") (part "TEST-POINT"))
    )
    (comp (ref "TP2")
      (value "TEST-POINT")
      (footprint "eagle-import:PAD.03X.03")
      (libsource (lib "eagle-import") (part "TEST-POINT"))
    )
    (comp (ref "TP3")
      (value "TEST-POINT")
      (footprint "eagle-import:PAD.03X.03")
      (libsource (lib "eagle-import") (part "TEST-POINT"))
    )
    (comp (ref "TP4")
      (value "TEST-POINT")
      (footprint "eagle-import:PAD.03X.03")
      (libsource (lib "eagle-import") (part "TEST-POINT"))
    )
    (comp (ref "TP5")
      (value "TEST-POINT")
      (footprint "eagle-import:PAD.03X.03")
      (libsource (lib "eagle-import") (part "TEST-POINT"))
    )
    (comp (ref "TP6")
      (value "TEST-POINT")
      (footprint "eagle-import:PAD.03X.03")
      (libsource (lib "eagle-import") (part "TEST-POINT"))
    )
    (comp (ref "TP7")
      (value "TEST-POINT")
      (footprint "eagle-import:PAD.03X.03")
      (libsource (lib "eagle-import") (part "TEST-POINT"))
    )
    (comp (ref "U2")
      (value "DW3110")
      (footprint "eagle-import:WLCSP52")
      (fields (field (name "MANUFACTURER") "Qorvo"))
      (libsource (lib "eagle-import") (part "DW3110"))
    )
    (comp (ref "U7")
      (value "QM14068")
      (footprint "eagle-import:QM14068")
      (fields (field (name "MANUFACTURER") "Qorvo"))
      (libsource (lib "eagle-import") (part "QM14068"))
    )
    (comp (ref "VR3")
      (value "TPS7A0218PDQNR")
      (footprint "eagle-import:4-XDFN-EP")
      (libsource (lib "eagle-import") (part "TPS7A0218PDQNR"))
    )
    (comp (ref "X4")
      (value "TXC-8Y")
      (footprint "eagle-import:TXC-8Y")
      (fields
        (field (name "FREQ") "38.4 MHz")
        (field (name "MANUFACTURER") "TXC")
        (field (name "MPN") "8Y38472012")
      )
      (libsource (lib "eagle-import") (part "TXC-8Y"))
    )
    (comp (ref "FD1")
      (value "FIDUCIAL")
      (footprint "eagle-import:FIDUCIAL_1MM-CU_2MM-MASK")
      (libsource (lib "eagle-import") (part "FIDUCIAL"))
    )
    (comp (ref "FD2")
      (value "FIDUCIAL")
      (footprint "eagle-import:FIDUCIAL_1MM-CU_2MM-MASK")
      (libsource (lib "eagle-import") (part "FIDUCIAL"))
    )
    (comp (ref "FD3")
      (value "FIDUCIAL")
      (footprint "eagle-import:FIDUCIAL_1MM-CU_2MM-MASK")
      (libsource (lib "eagle-import") (part "FIDUCIAL"))
    )
    (comp (ref "FD4")
      (value "FIDUCIAL")
      (footprint "eagle-import:FIDUCIAL_1MM-CU_2MM-MASK")
      (libsource (lib "eagle-import") (part "FIDUCIAL"))
    )
    (comp (ref "C51")
      (value "1uF")
      (footprint "eagle-import:0201_CAP")
      (fields (field (name "MANUFACTURER") "Murata") (field (name "MPN") "GRM033R61A105ME44D"))
      (libsource (lib "eagle-import") (part "passives_20904581_CAPACITOR0201_CAP"))
    )
    (comp (ref "C52")
      (value "1uF")
      (footprint "eagle-import:0201_CAP")
      (fields (field (name "MANUFACTURER") "Murata") (field (name "MPN") "GRM033R61A105ME44D"))
      (libsource (lib "eagle-import") (part "passives_20904581_CAPACITOR0201_CAP"))
    )
    (comp (ref "C68")
      (value "1uF")
      (footprint "eagle-import:0201_CAP")
      (fields (field (name "MANUFACTURER") "Murata") (field (name "MPN") "GRM033R61A105ME44D"))
      (libsource (lib "eagle-import") (part "passives_20904581_CAPACITOR0201_CAP"))
    )
    (comp (ref "C77")
      (value "1uF")
      (footprint "eagle-import:0201_CAP")
      (fields (field (name "MANUFACTURER") "Murata") (field (name "MPN") "GRM033R61A105ME44D"))
      (libsource (lib "eagle-import") (part "passives_20904581_CAPACITOR0201_CAP"))
    )
    (comp (ref "C78")
      (value "1uF")
      (footprint "eagle-import:0201_CAP")
      (fields (field (name "MANUFACTURER") "Murata") (field (name "MPN") "GRM033R61A105ME44D"))
      (libsource (lib "eagle-import") (part "passives_20904581_CAPACITOR0201_CAP"))
    )
    (comp (ref "C82")
      (value "1uF")
      (footprint "eagle-import:0201_CAP")
      (fields (field (name "MANUFACTURER") "Murata") (field (name "MPN") "GRM033R61A105ME44D"))
      (libsource (lib "eagle-import") (part "passives_20904581_CAPACITOR0201_CAP"))
    )
    (comp (ref "D1")
      (value "BICOLOR-SMD")
      (footprint "eagle-import:LED-0606")
      (fields (field (name "MPN") "MCL0606FRD1GR1T"))
      (libsource (lib "eagle-import") (part "BICOLOR-SMD"))
    )
    (comp (ref "D2")
      (value "BICOLOR-SMD")
      (footprint "eagle-import:LED-0606")
      (fields (field (name "MPN") "MCL0606FYW1RD1T"))
      (libsource (lib "eagle-import") (part "BICOLOR-SMD"))
    )
    (comp (ref "D5")
      (value "DIODE_TVS_ARRAY-2")
      (footprint "eagle-import:SOT143B")
      (fields (field (name "MPN") "PRTR5V0U2X,215"))
      (libsource (lib "eagle-import") (part "DIODE_TVS_ARRAY-2"))
    )
    (comp (ref "J1")
      (value "TC2030-JLINK-NL-2SIDE")
      (footprint "eagle-import:TC2030-IDC-NL-2SIDE")
      (libsource (lib "eagle-import") (part "TC2030-JLINK-NL-2SIDE"))
    )
    (comp (ref "R2")
      (value "5.1")
      (footprint "eagle-import:0402_RES")
      (fields (field (name "MPN") "RC0402JR-075R1L"))
      (libsource (lib "eagle-import") (part "RESISTOR0402_RES"))
    )
    (comp (ref "R3")
      (value "5.1")
      (footprint "eagle-import:0402_RES")
      (fields (field (name "MPN") "RC0402JR-075R1L"))
      (libsource (lib "eagle-import") (part "RESISTOR0402_RES"))
    )
    (comp (ref "R4")
      (value "15")
      (footprint "eagle-import:0402_RES")
      (fields (field (name "MPN") "RC0402JR-0715RL"))
      (libsource (lib "eagle-import") (part "RESISTOR0402_RES"))
    )
    (comp (ref "R5")
      (value "15")
      (footprint "eagle-import:0402_RES")
      (fields (field (name "MPN") "RC0402JR-0715RL"))
      (libsource (lib "eagle-import") (part "RESISTOR0402_RES"))
    )
    (comp (ref "R23")
      (value "402k")
      (footprint "eagle-import:0201_RES")
      (fields (field (name "MPN") "ERJ-1GNF4023C"))
      (libsource (lib "eagle-import") (part "passives_20904581_RESISTOR0201_RES"))
    )
    (comp (ref "R26")
      (value "845k")
      (footprint "eagle-import:0201_RES")
      (fields (field (name "MPN") "ERJ-1GNF8453C"))
      (libsource (lib "eagle-import") (part "passives_20904581_RESISTOR0201_RES"))
    )
    (comp (ref "RZ3")
      (value "0")
      (footprint "eagle-import:0402_RES")
      (fields (field (name "MPN") "RMCF0402ZT0R00"))
      (libsource (lib "eagle-import") (part "passives_20904581_RESISTOR0402_RES"))
    )
    (comp (ref "RZ5")
      (value "0")
      (footprint "eagle-import:0402_RES")
      (fields (field (name "MPN") "RMCF0402ZT0R00"))
      (libsource (lib "eagle-import") (part "passives_20904581_RESISTOR0402_RES"))
    )
    (comp (ref "SJ7")
      (value "JUMPER-SMT_2_NC_TRACE_SILK")
      (footprint "eagle-import:SMT-JUMPER_2_NC_TRACE_SILK")
      (libsource (lib "eagle-import") (part "JUMPER-SMT_2_NC_TRACE_SILK"))
    )
    (comp (ref "VR2")
      (value "TPS7A0218PDQNR")
      (footprint "eagle-import:4-XDFN-EP")
      (libsource (lib "eagle-import") (part "TPS7A0218PDQNR"))
    )
    (comp (ref "VR4")
      (value "TPS7A0233PDQNR")
      (footprint "eagle-import:4-XDFN-EP")
      (libsource (lib "eagle-import") (part "TPS7A0233PDQNR"))
    )
    (comp (ref "VR5")
      (value "TPS7A0309PDBVR")
      (footprint "eagle-import:DBV0005A--SOT23-5-VARIANT")
      (libsource (lib "eagle-import") (part "TPS7A0309PDBVR"))
    )
    (comp (ref "A4")
      (value "AMCA72-2R47G-S1F-T")
      (footprint "eagle-import:AMCA72-2R470G-S1F-T")
      (fields (field (name "MPN") "AMCA72-2R470G-S1F-T4"))
      (libsource (lib "eagle-import") (part "AMCA72-2R47G-S1F-T"))
    )
    (comp (ref "C1")
      (value "1.5pF")
      (footprint "eagle-import:CAPC1005X60")
      (description "CAP CER 1.5PF 50V C0G/NP0 0402")
      (fields
        (field (name "MANUFACTURER") "KEMET")
        (field (name "MPN") "C0402C159C5GACTU")
        (field (name "TEMPCOEFF") "NP0")
        (field (name "TOLERANCE") "+/- 0.25pF")
      )
      (libsource (lib "eagle-import") (part "CCHIP-0402(1005-METRIC)_"))
    )
    (comp (ref "C58")
      (value "2.2uF")
      (footprint "eagle-import:0201_CAP")
      (fields (field (name "MANUFACTURER") "Murata") (field (name "MPN") "GRM033R61A225KE47D"))
      (libsource (lib "eagle-import") (part "passives_20904581_CAPACITOR0201_CAP"))
    )
    (comp (ref "C59")
      (value "2.2uF")
      (footprint "eagle-import:0201_CAP")
      (fields (field (name "MANUFACTURER") "Murata") (field (name "MPN") "GRM033R61A225KE47D"))
      (libsource (lib "eagle-import") (part "passives_20904581_CAPACITOR0201_CAP"))
    )
    (comp (ref "C60")
      (value "2.2uF")
      (footprint "eagle-import:0201_CAP")
      (fields (field (name "MANUFACTURER") "Murata") (field (name "MPN") "GRM033R61A225KE47D"))
      (libsource (lib "eagle-import") (part "passives_20904581_CAPACITOR0201_CAP"))
    )
    (comp (ref "C61")
      (value "2.2uF")
      (footprint "eagle-import:0201_CAP")
      (fields (field (name "MANUFACTURER") "Murata") (field (name "MPN") "GRM033R61A225KE47D"))
      (libsource (lib "eagle-import") (part "passives_20904581_CAPACITOR0201_CAP"))
    )
    (comp (ref "C62")
      (value "1uF")
      (footprint "eagle-import:0201_CAP")
      (fields (field (name "MANUFACTURER") "Murata") (field (name "MPN") "GRM033R61A105ME44D"))
      (libsource (lib "eagle-import") (part "passives_20904581_CAPACITOR0201_CAP"))
    )
    (comp (ref "C63")
      (value "1uF")
      (footprint "eagle-import:0201_CAP")
      (fields (field (name "MANUFACTURER") "Murata") (field (name "MPN") "GRM033R61A105ME44D"))
      (libsource (lib "eagle-import") (part "passives_20904581_CAPACITOR0201_CAP"))
    )
    (comp (ref "C64")
      (value "1uF")
      (footprint "eagle-import:0201_CAP")
      (fields (field (name "MANUFACTURER") "Murata") (field (name "MPN") "GRM033R61A105ME44D"))
      (libsource (lib "eagle-import") (part "passives_20904581_CAPACITOR0201_CAP"))
    )
    (comp (ref "C65")
      (value "1uF")
      (footprint "eagle-import:0201_CAP")
      (fields (field (name "MANUFACTURER") "Murata") (field (name "MPN") "GRM033R61A105ME44D"))
      (libsource (lib "eagle-import") (part "passives_20904581_CAPACITOR0201_CAP"))
    )
    (comp (ref "C66")
      (value "2.2uF")
      (footprint "eagle-import:0201_CAP")
      (fields (field (name "MANUFACTURER") "Murata") (field (name "MPN") "GRM033R61A225KE47D"))
      (libsource (lib "eagle-import") (part "passives_20904581_CAPACITOR0201_CAP"))
    )
    (comp (ref "C67")
      (value "2.2uF")
      (footprint "eagle-import:0201_CAP")
      (fields (field (name "MANUFACTURER") "Murata") (field (name "MPN") "GRM033R61A225KE47D"))
      (libsource (lib "eagle-import") (part "passives_20904581_CAPACITOR0201_CAP"))
    )
    (comp (ref "C69")
      (value "4.7uF")
      (footprint "eagle-import:0402_CAP")
      (fields (field (name "MPN") "CL05A475MP5NRNC"))
      (libsource (lib "eagle-import") (part "CAPACITOR0402_CAP"))
    )
    (comp (ref "C70")
      (value "2.2uF")
      (footprint "eagle-import:0201_CAP")
      (fields (field (name "MANUFACTURER") "Murata") (field (name "MPN") "GRM033R61A225KE47D"))
      (libsource (lib "eagle-import") (part "passives_20904581_CAPACITOR0201_CAP"))
    )
    (comp (ref "C71")
      (value "2.2uF")
      (footprint "eagle-import:0201_CAP")
      (fields (field (name "MANUFACTURER") "Murata") (field (name "MPN") "GRM033R61A225KE47D"))
      (libsource (lib "eagle-import") (part "passives_20904581_CAPACITOR0201_CAP"))
    )
    (comp (ref "C72")
      (value "2.2uF")
      (footprint "eagle-import:0201_CAP")
      (fields (field (name "MANUFACTURER") "Murata") (field (name "MPN") "GRM033R61A225KE47D"))
      (libsource (lib "eagle-import") (part "passives_20904581_CAPACITOR0201_CAP"))
    )
    (comp (ref "C73")
      (value "2.2uF")
      (footprint "eagle-import:0201_CAP")
      (fields (field (name "MANUFACTURER") "Murata") (field (name "MPN") "GRM033R61A225KE47D"))
      (libsource (lib "eagle-import") (part "passives_20904581_CAPACITOR0201_CAP"))
    )
    (comp (ref "C74")
      (value "2.2uF")
      (footprint "eagle-import:0201_CAP")
      (fields (field (name "MANUFACTURER") "Murata") (field (name "MPN") "GRM033R61A225KE47D"))
      (libsource (lib "eagle-import") (part "passives_20904581_CAPACITOR0201_CAP"))
    )
    (comp (ref "C75")
      (value "2.2uF")
      (footprint "eagle-import:0201_CAP")
      (fields (field (name "MANUFACTURER") "Murata") (field (name "MPN") "GRM033R61A225KE47D"))
      (libsource (lib "eagle-import") (part "passives_20904581_CAPACITOR0201_CAP"))
    )
    (comp (ref "C76")
      (value "4700pF")
      (footprint "eagle-import:CAPC1005X60")
      (fields (field (name "MPN") "KGM05AR71E472KH"))
      (libsource (lib "eagle-import") (part "CCHIP-0402(1005-METRIC)_"))
    )
    (comp (ref "C79")
      (value "1uF")
      (footprint "eagle-import:0201_CAP")
      (fields (field (name "MANUFACTURER") "MURATA") (field (name "MPN") "GRM033R61A105ME44D"))
      (libsource (lib "eagle-import") (part "passives_20904581_CAPACITOR0201_CAP"))
    )
    (comp (ref "C80")
      (value "6pF")
      (footprint "eagle-import:CAPC1005X60")
      (fields (field (name "MANUFACTURER") "Murata") (field (name "MPN") "GCM1555C1H6R0BA16D"))
      (libsource (lib "eagle-import") (part "CCHIP-0402(1005-METRIC)_"))
    )
    (comp (ref "C81")
      (value "6pF")
      (footprint "eagle-import:CAPC1005X60")
      (fields (field (name "MANUFACTURER") "Murata") (field (name "MPN") "GCM1555C1H6R0BA16D"))
      (libsource (lib "eagle-import") (part "CCHIP-0402(1005-METRIC)_"))
    )
    (comp (ref "C93")
      (value "1uF")
      (footprint "eagle-import:0201_CAP")
      (fields (field (name "MANUFACTURER") "Murata") (field (name "MPN") "GRM033R61A105ME44D"))
      (libsource (lib "eagle-import") (part "passives_20904581_CAPACITOR0201_CAP"))
    )
    (comp (ref "CX1")
      (value "DNP")
      (footprint "eagle-import:CAPC1005X60")
      (libsource (lib "eagle-import") (part "CCHIP-0402(1005-METRIC)_"))
    )
    (comp (ref "CX2")
      (value "DNP")
      (footprint "eagle-import:CAPC1005X60")
      (libsource (lib "eagle-import") (part "CCHIP-0402(1005-METRIC)_"))
    )
    (comp (ref "D3")
      (value "ZENER")
      (footprint "eagle-import:SODFL1608X70")
      (description "DIODE TVS 5.5V STANDOFF 8V BREAKDOWN SC79")
      (fields (field (name "MANUFACTURER") "NXP SEMICONDUCTOR") (field (name "MPN") "PESD5V0X1UB,135"))
      (libsource (lib "eagle-import") (part "ZENERSODFL(1608-METRIC)_"))
    )
    (comp (ref "L5")
      (value "2.2µH")
      (footprint "eagle-import:0805_CAP")
      (fields (field (name "MANUFACTURER") "Murata") (field (name "MPN") "DFE201210U-2R2M=P2"))
      (libsource (lib "eagle-import") (part "INDUCTOR0805"))
    )
    (comp (ref "L6")
      (value "1.0µH")
      (footprint "eagle-import:0603_CAP")
      (fields (field (name "MANUFACTURER") "Taiyo Yuden") (field (name "MPN") "MCKK1608T1R0MN"))
      (libsource (lib "eagle-import") (part "INDUCTOR0603"))
    )
    (comp (ref "L7")
      (value "2.0nH")
      (footprint "eagle-import:INDC1006X60N")
      (description "FIXED IND 2.0NH0.1NH SMD")
      (fields
        (field (name "MANUFACTURER") "Murata")
        (field (name "MPN") "LQG15HS2N0B02D")
        (field (name "TOLERANCE") "+/- 0.1 nH")
      )
      (libsource (lib "eagle-import") (part "LCHIP-0402(1006-METRIC)_"))
    )
    (comp (ref "L8")
      (value "2.2nH")
      (footprint "eagle-import:INDC1006X60N")
      (description "FIXED IND 2.2NH0.1NH SMD")
      (fields
        (field (name "MANUFACTURER") "Murata")
        (field (name "MPN") "LQG15HN2N2B02D")
        (field (name "TOLERANCE") "+/- 0.1 nH")
      )
      (libsource (lib "eagle-import") (part "LCHIP-0402(1006-METRIC)_"))
    )
    (comp (ref "RZ6")
      (value "0")
      (footprint "eagle-import:0402_RES")
      (fields (field (name "MPN") "RMCF0402ZT0R00"))
      (libsource (lib "eagle-import") (part "passives_20904581_RESISTOR0402_RES"))
    )
    (comp (ref "TP8")
      (value "VDDBH")
      (footprint "eagle-import:PAD.03X.03")
      (libsource (lib "eagle-import") (part "TEST-POINT"))
    )
    (comp (ref "TP9")
      (value "VDDP")
      (footprint "eagle-import:PAD.03X.03")
      (libsource (lib "eagle-import") (part "TEST-POINT"))
    )
    (comp (ref "TP10")
      (value "VDDF")
      (footprint "eagle-import:PAD.03X.03")
      (libsource (lib "eagle-import") (part "TEST-POINT"))
    )
    (comp (ref "U1")
      (value "APOLLO4_BLUE_PLUS_SOC_KBR")
      (footprint "eagle-import:APOLLO4_BLUE_SOC_BGA")
      (fields (field (name "MANUFACTURER") "Ambiq") (field (name "MPN") "AMA4B2KP-KBR"))
      (libsource (lib "eagle-import") (part "APOLLO4_BLUE_PLUS_SOC_KBR"))
    )
    (comp (ref "X1")
      (value "ABM12W")
      (footprint "eagle-import:ABM12W")
      (fields
        (field (name "C-LOAD") "6pF")
        (field (name "FREQUENCY") "32 MHz")
        (field (name "MANUFACTURER") "Abracon")
        (field (name "MAX-ESR") "80Ω")
        (field (name "MPN") "ABM12W-32.0000MHZ-6-D1X-T3")
      )
      (libsource (lib "eagle-import") (part "ABM12W"))
    )
    (comp (ref "X3")
      (value "TXC-9HT12")
      (footprint "eagle-import:TXC-9HT12")
      (fields
        (field (name "C-LOAD") "7pF")
        (field (name "FREQUENCY") "32.768 kHz")
        (field (name "MANUFACTURER") "TXC Corp")
        (field (name "MPN") "9HT12-32.768KDZY-T")
      )
      (libsource (lib "eagle-import") (part "TXC-9HT12"))
    )
  )
  (nets
    (net (code "1") (name "+1V8") (class "Default")
      (node (ref "C26") (pin "1") (pinfunction "1_1") (pintype "bidirectional"))
      (node (ref "C31") (pin "1") (pinfunction "1_1") (pintype "bidirectional"))
      (node (ref "C35") (pin "1") (pinfunction "1_1") (pintype "bidirectional"))
      (node (ref "C46") (pin "1") (pinfunction "1_1") (pintype "bidirectional"))
      (node (ref "C50") (pin "2") (pinfunction "2_2") (pintype "bidirectional"))
      (node (ref "C62") (pin "P$1") (pinfunction "1_P$1") (pintype "bidirectional"))
      (node (ref "C63") (pin "P$1") (pinfunction "1_P$1") (pintype "bidirectional"))
      (node (ref "C64") (pin "P$1") (pinfunction "1_P$1") (pintype "bidirectional"))
      (node (ref "C65") (pin "P$1") (pinfunction "1_P$1") (pintype "bidirectional"))
      (node (ref "C66") (pin "P$1") (pinfunction "1_P$1") (pintype "bidirectional"))
      (node (ref "C67") (pin "P$1") (pinfunction "1_P$1") (pintype "bidirectional"))
      (node (ref "C75") (pin "P$2") (pinfunction "2_P$2") (pintype "bidirectional"))
      (node (ref "C8") (pin "P$2") (pinfunction "2_P$2") (pintype "bidirectional"))
      (node (ref "D1") (pin "A1") (pinfunction "A1_A1") (pintype "bidirectional"))
      (node (ref "D1") (pin "A2") (pinfunction "A2_A2") (pintype "bidirectional"))
      (node (ref "D2") (pin "A1") (pinfunction "A1_A1") (pintype "bidirectional"))
      (node (ref "D2") (pin "A2") (pinfunction "A2_A2") (pintype "bidirectional"))
      (node (ref "J1") (pin "1") (pinfunction "VTREF_1") (pintype "bidirectional"))
      (node (ref "J1") (pin "B1") (pinfunction "VTREF_B1") (pintype "bidirectional"))
      (node (ref "J6") (pin "1") (pinfunction "1_1") (pintype "passive"))
      (node (ref "L2") (pin "P$1") (pinfunction "1_P$1") (pintype "bidirectional"))
      (node (ref "R14") (pin "2") (pinfunction "2_2") (pintype "passive"))
      (node (ref "R15") (pin "2") (pinfunction "2_2") (pintype "passive"))
      (node (ref "R16") (pin "2") (pinfunction "2_2") (pintype "passive"))
      (node (ref "R25") (pin "1") (pinfunction "1_1") (pintype "passive"))
      (node (ref "RX3") (pin "2") (pinfunction "2_2") (pintype "passive"))
      (node (ref "RX4") (pin "1") (pinfunction "1_1") (pintype "passive"))
      (node (ref "RX5") (pin "1") (pinfunction "1_1") (pintype "passive"))
      (node (ref "S3") (pin "4") (pinfunction "IN_4") (pintype "bidirectional"))
      (node (ref "SJ2") (pin "1") (pinfunction "1_1") (pintype "passive"))
      (node (ref "SJ4") (pin "3") (pinfunction "3_3") (pintype "passive"))
      (node (ref "TP9") (pin "P$1") (pinfunction "TESTPOINT_P$1") (pintype "bidirectional"))
      (node (ref "U1") (pin "B1") (pinfunction "VDDP-IO_PAD_SUP_B1") (pintype "bidirectional"))
      (node (ref "U1") (pin "C4") (pinfunction "VDDA-ANALOG_SUP_C4") (pintype "bidirectional"))
      (node (ref "U1") (pin "E11") (pinfunction "VDDAUDD_E11") (pintype "bidirectional"))
      (node (ref "U1") (pin "G1") (pinfunction "VDDB-BLE_SUPPLY_G1") (pintype "bidirectional"))
      (node (ref "U1") (pin "M10") (pinfunction "VDDH-HV_SUP_M10") (pintype "bidirectional"))
      (node (ref "U1") (pin "M9") (pinfunction "VDDH2-HV_SUP_M9") (pintype "bidirectional"))
      (node (ref "U2") (pin "B13") (pinfunction "VDD1_B13") (pintype "bidirectional"))
      (node (ref "U6") (pin "28") (pinfunction "VDDIO_28") (pintype "input"))
      (node (ref "U8") (pin "8") (pinfunction "VCC_8") (pintype "bidirectional"))
    )
    (net (code "2") (name "+2V5") (class "Default")
      (node (ref "C32") (pin "1") (pinfunction "1_1") (pintype "bidirectional"))
      (node (ref "C34") (pin "1") (pinfunction "1_1") (pintype "bidirectional"))
      (node (ref "C44") (pin "1") (pinfunction "1_1") (pintype "bidirectional"))
      (node (ref "C47") (pin "2") (pinfunction "2_2") (pintype "bidirectional"))
      (node (ref "C49") (pin "1") (pinfunction "1_1") (pintype "bidirectional"))
      (node (ref "C7") (pin "P$1") (pinfunction "1_P$1") (pintype "bidirectional"))
      (node (ref "C77") (pin "P$1") (pinfunction "1_P$1") (pintype "bidirectional"))
      (node (ref "C90") (pin "P$1") (pinfunction "1_P$1") (pintype "bidirectional"))
      (node (ref "D4") (pin "CATHODE") (pinfunction "CATHODE_CATHODE") (pintype "bidirectional"))
      (node (ref "J5") (pin "1") (pinfunction "1_1") (pintype "passive"))
      (node (ref "L1") (pin "P$2") (pinfunction "2_P$2") (pintype "bidirectional"))
      (node (ref "LS1") (pin "+") (pinfunction "P_+") (pintype "passive"))
      (node (ref "R24") (pin "2") (pinfunction "2_2") (pintype "passive"))
      (node (ref "S2") (pin "6") (pinfunction "VDD_6") (pintype "power_in"))
      (node (ref "S3") (pin "1") (pinfunction "IN_1") (pintype "bidirectional"))
      (node (ref "U6") (pin "3") (pinfunction "VDD_3") (pintype "input"))
      (node (ref "VR2") (pin "3") (pinfunction "EN_3") (pintype "input"))
      (node (ref "VR2") (pin "4") (pinfunction "IN_4") (pintype "bidirectional"))
      (node (ref "VR3") (pin "4") (pinfunction "IN_4") (pintype "bidirectional"))
    )
    (net (code "3") (name "9DOF_H_SDA{slash}H_MISO{slash}TX") (class "Default")
      (node (ref "RX4") (pin "2") (pinfunction "2_2") (pintype "passive"))
      (node (ref "SJ5") (pin "1") (pinfunction "1_1") (pintype "passive"))
      (node (ref "SJ6") (pin "2") (pinfunction "2_2") (pintype "passive"))
      (node (ref "U6") (pin "20") (pinfunction "H_SDA/H_MISO/TX_20") (pintype "bidirectional"))
    )
    (net (code "4") (name "9DOF_SA0{slash}H_MOSI") (class "Default")
      (node (ref "SJ5") (pin "2") (pinfunction "2_2") (pintype "passive"))
      (node (ref "SJ6") (pin "1") (pinfunction "1_1") (pintype "passive"))
      (node (ref "U6") (pin "17") (pinfunction "SA0/H_MOSI_17") (pintype "input"))
    )
    (net (code "5") (name "AGND") (class "Default")
      (node (ref "C1") (pin "2") (pinfunction "2_2") (pintype "passive"))
      (node (ref "C93") (pin "P$2") (pinfunction "2_P$2") (pintype "bidirectional"))
      (node (ref "U1") (pin "M1") (pinfunction "RFIOM_M1") (pintype "bidirectional"))
      (node (ref "U1") (pin "M3") (pinfunction "RFSUB-RF_SUBSTRATE_GND_M3") (pintype "bidirectional"))
    )
    (net (code "6") (name "AP4_GP06{slash}TT_FLASH_~{HOLD_IO3}") (class "Default")
      (node (ref "U1") (pin "J5") (pinfunction "GPIO6_J5") (pintype "bidirectional"))
      (node (ref "U8") (pin "7") (pinfunction "~{HOLD}/SIO3_7") (pintype "bidirectional"))
    )
    (net (code "7") (name "AP4_GP08{slash}TT_9DOF_H_SCL{slash}SCK{slash}RX") (class "Default")
      (node (ref "RX5") (pin "2") (pinfunction "2_2") (pintype "passive"))
      (node (ref "U1") (pin "H2") (pinfunction "GPIO31_H2") (pintype "bidirectional"))
      (node (ref "U6") (pin "19") (pinfunction "H_SCL/SCK/RX_19") (pintype "bidirectional"))
    )
    (net (code "8") (name "AP4_GP09{slash}TT_9DOF_H_MOSI") (class "Default")
      (node (ref "SJ5") (pin "3") (pinfunction "3_3") (pintype "passive"))
      (node (ref "U1") (pin "G2") (pinfunction "GPIO32_G2") (pintype "bidirectional"))
    )
    (net (code "9") (name "AP4_GP10{slash}TT_9DOF_H_MISO") (class "Default")
      (node (ref "SJ6") (pin "3") (pinfunction "3_3") (pintype "passive"))
      (node (ref "U1") (pin "G3") (pinfunction "GPIO33_G3") (pintype "bidirectional"))
    )
    (net (code "10") (name "AP4_GP13{slash}TT_9DOF_~{BOOT}") (class "Default")
      (node (ref "R14") (pin "1") (pinfunction "1_1") (pintype "passive"))
      (node (ref "U1") (pin "D5") (pinfunction "GPIO13_D5") (pintype "bidirectional"))
      (node (ref "U6") (pin "4") (pinfunction "~{BOOT}_4") (pintype "input"))
    )
    (net (code "11") (name "AP4_GP14{slash}TT_~{DW_SPI_CS}") (class "Default")
      (node (ref "U1") (pin "D6") (pinfunction "GPIO14_D6") (pintype "bidirectional"))
      (node (ref "U2") (pin "B5") (pinfunction "~{SPICS}_B5") (pintype "bidirectional"))
    )
    (net (code "12") (name "AP4_GP17{slash}TT_9DOF_H_~{INT}") (class "Default")
      (node (ref "U1") (pin "D4") (pinfunction "GPIO17_D4") (pintype "bidirectional"))
      (node (ref "U6") (pin "14") (pinfunction "H_INTN_14") (pintype "output"))
    )
    (net (code "13") (name "AP4_GP18{slash}TT_BATIN") (class "Default")
      (node (ref "C27") (pin "1") (pinfunction "1_1") (pintype "bidirectional"))
      (node (ref "R27") (pin "2") (pinfunction "2_2") (pintype "passive"))
      (node (ref "R28") (pin "1") (pinfunction "1_1") (pintype "passive"))
      (node (ref "U1") (pin "D3") (pinfunction "GPIO18_D3") (pintype "bidirectional"))
    )
    (net (code "14") (name "AP4_GP24{slash}TT_RFSW_V1") (class "Default")
      (node (ref "S2") (pin "4") (pinfunction "V1_4") (pintype "input"))
      (node (ref "U1") (pin "E2") (pinfunction "GPIO24_E2") (pintype "bidirectional"))
    )
    (net (code "15") (name "AP4_GP25{slash}TT_RFSW_V2") (class "Default")
      (node (ref "S2") (pin "5") (pinfunction "V2_5") (pintype "input"))
      (node (ref "U1") (pin "K5") (pinfunction "GPIO25_K5") (pintype "bidirectional"))
    )
    (net (code "16") (name "AP4_GP26{slash}TT_DW_WAKEUP") (class "Default")
      (node (ref "U1") (pin "L5") (pinfunction "GPIO26_L5") (pintype "bidirectional"))
      (node (ref "U2") (pin "B9") (pinfunction "WAKEUP_B9") (pintype "bidirectional"))
    )
    (net (code "17") (name "AP4_GP27{slash}TT_DW_IRQ") (class "Default")
      (node (ref "R19") (pin "2") (pinfunction "2_2") (pintype "passive"))
      (node (ref "U1") (pin "M5") (pinfunction "GPIO27_M5") (pintype "bidirectional"))
      (node (ref "U2") (pin "B1") (pinfunction "IRQ/GPIO8_B1") (pintype "bidirectional"))
    )
    (net (code "18") (name "AP4_GP30{slash}TT_FLASH_~{WP}") (class "Default")
      (node (ref "U1") (pin "G4") (pinfunction "GPIO30_G4") (pintype "bidirectional"))
      (node (ref "U8") (pin "3") (pinfunction "~{WP}/SIO2_3") (pintype "bidirectional"))
    )
    (net (code "19") (name "AP4_GP31{slash}TT_DW_SPI_CLK") (class "Default")
      (node (ref "U1") (pin "E8") (pinfunction "GPIO8_E8") (pintype "bidirectional"))
      (node (ref "U2") (pin "A8") (pinfunction "SPICLK_A8") (pintype "bidirectional"))
    )
    (net (code "20") (name "AP4_GP32{slash}TT_DW_SPI_IO0") (class "Default")
      (node (ref "U1") (pin "E7") (pinfunction "GPIO9_E7") (pintype "bidirectional"))
      (node (ref "U2") (pin "B7") (pinfunction "SPICDI(MOSI)_B7") (pintype "bidirectional"))
    )
    (net (code "21") (name "AP4_GP33{slash}TT_DW_SPI_IO1") (class "Default")
      (node (ref "U1") (pin "E6") (pinfunction "GPIO10_E6") (pintype "bidirectional"))
      (node (ref "U2") (pin "A6") (pinfunction "SPICDO(MISO)_A6") (pintype "bidirectional"))
    )
    (net (code "22") (name "AP4_GP47{slash}TT_FLASH_SCK") (class "Default")
      (node (ref "U1") (pin "F1") (pinfunction "GPIO47_F1") (pintype "bidirectional"))
      (node (ref "U8") (pin "6") (pinfunction "SCLK_6") (pintype "input"))
    )
    (net (code "23") (name "AP4_GP48{slash}TT_FLASH_PDI_IO0") (class "Default")
      (node (ref "U1") (pin "E1") (pinfunction "GPIO48_E1") (pintype "bidirectional"))
      (node (ref "U8") (pin "5") (pinfunction "SI/SIO0_5") (pintype "bidirectional"))
    )
    (net (code "24") (name "AP4_GP49{slash}TT_FLASH_PDO_IO1") (class "Default")
      (node (ref "U1") (pin "D1") (pinfunction "GPIO49_D1") (pintype "bidirectional"))
      (node (ref "U8") (pin "2") (pinfunction "SO/SIO1_2") (pintype "bidirectional"))
    )
    (net (code "25") (name "AP4_GP50{slash}TT_~{DW_RESET}") (class "Default")
      (node (ref "U1") (pin "A9") (pinfunction "GPIO50_A9") (pintype "bidirectional"))
      (node (ref "U2") (pin "A10") (pinfunction "~{RST}_A10") (pintype "bidirectional"))
    )
    (net (code "26") (name "AP4_GP51{slash}LED1_GREEN") (class "Default")
      (node (ref "R2") (pin "2") (pinfunction "2_2") (pintype "passive"))
      (node (ref "U1") (pin "B9") (pinfunction "GPIO51_B9") (pintype "bidirectional"))
    )
    (net (code "27") (name "AP4_GP53{slash}LED1_RED") (class "Default")
      (node (ref "R5") (pin "2") (pinfunction "2_2") (pintype "passive"))
      (node (ref "U1") (pin "C9") (pinfunction "GPIO53_C9") (pintype "bidirectional"))
    )
    (net (code "28") (name "AP4_GP55{slash}TT_BUZZER_GATE") (class "Default")
      (node (ref "Q2") (pin "G") (pinfunction "G_G") (pintype "passive"))
      (node (ref "R20") (pin "1") (pinfunction "1_1") (pintype "passive"))
      (node (ref "U1") (pin "D9") (pinfunction "GPIO55_D9") (pintype "bidirectional"))
    )
    (net (code "29") (name "AP4_GP58{slash}TT_~{CHG}") (class "Default")
      (node (ref "U1") (pin "J7") (pinfunction "GPIO58_J7") (pintype "bidirectional"))
      (node (ref "U3") (pin "8") (pinfunction "~{CHG}_8") (pintype "bidirectional"))
      (node (ref "U4") (pin "7") (pinfunction "~{CHG}_7") (pintype "bidirectional"))
    )
    (net (code "30") (name "AP4_GP60{slash}TT_~{PG}") (class "Default")
      (node (ref "U1") (pin "K8") (pinfunction "GPIO60_K8") (pintype "bidirectional"))
      (node (ref "U3") (pin "5") (pinfunction "~{PG}_5") (pintype "bidirectional"))
    )
    (net (code "31") (name "AP4_GP63{slash}TT_9DOF_PS0{slash}WAKE") (class "Default")
      (node (ref "U1") (pin "M6") (pinfunction "GPIO63_M6") (pintype "bidirectional"))
      (node (ref "U6") (pin "6") (pinfunction "PS0/WAKE_6") (pintype "input"))
    )
    (net (code "32") (name "AP4_GP65{slash}TT_9DOF_~{RESET}") (class "Default")
      (node (ref "U1") (pin "A7") (pinfunction "GPIO65_A7") (pintype "bidirectional"))
      (node (ref "U6") (pin "11") (pinfunction "~{RESET}_11") (pintype "input"))
    )
    (net (code "33") (name "AP4_GP66{slash}TT_QI_TS_CTRL") (class "Default")
      (node (ref "C30") (pin "1") (pinfunction "1_1") (pintype "bidirectional"))
      (node (ref "RT1") (pin "2") (pinfunction "2_2") (pintype "passive"))
      (node (ref "U1") (pin "A8") (pinfunction "GPIO66_A8") (pintype "bidirectional"))
      (node (ref "U4") (pin "13") (pinfunction "TS/CTRL_13") (pintype "bidirectional"))
    )
    (net (code "34") (name "AP4_GP69{slash}TT_FLASH_~{CS}") (class "Default")
      (node (ref "RX3") (pin "1") (pinfunction "1_1") (pintype "passive"))
      (node (ref "U1") (pin "B8") (pinfunction "GPIO69_B8") (pintype "bidirectional"))
      (node (ref "U8") (pin "1") (pinfunction "~{CS}_1") (pintype "input"))
    )
    (net (code "35") (name "AP4_GP72{slash}TT_9DOF_H_~{CS}") (class "Default")
      (node (ref "U1") (pin "C8") (pinfunction "GPIO72_C8") (pintype "bidirectional"))
      (node (ref "U6") (pin "18") (pinfunction "H_~{CS}_18") (pintype "input"))
    )
    (net (code "36") (name "AP4_GP78{slash}VR-EN_USB0P9") (class "Default")
      (node (ref "U1") (pin "L11") (pinfunction "GPIO78_L11") (pintype "bidirectional"))
      (node (ref "VR5") (pin "3") (pinfunction "EN_3") (pintype "input"))
    )
    (net (code "37") (name "AP4_GP79{slash}LED2_RED") (class "Default")
      (node (ref "R4") (pin "2") (pinfunction "2_2") (pintype "passive"))
      (node (ref "U1") (pin "M11") (pinfunction "GPIO79_M11") (pintype "bidirectional"))
    )
    (net (code "38") (name "AP4_GP80{slash}USB_CABLE_DETECT") (class "Default")
      (node (ref "R23") (pin "2") (pinfunction "2_2") (pintype "passive"))
      (node (ref "R26") (pin "1") (pinfunction "1_1") (pintype "passive"))
      (node (ref "U1") (pin "K10") (pinfunction "GPIO80_K10") (pintype "bidirectional"))
    )
    (net (code "39") (name "AP4_GP81{slash}VR-EN_USB3P3") (class "Default")
      (node (ref "U1") (pin "L10") (pinfunction "GPIO81_L10") (pintype "bidirectional"))
      (node (ref "VR4") (pin "3") (pinfunction "EN_3") (pintype "input"))
    )
    (net (code "40") (name "AP4_GP88{slash}LED2_YLW") (class "Default")
      (node (ref "R3") (pin "2") (pinfunction "2_2") (pintype "passive"))
      (node (ref "U1") (pin "F9") (pinfunction "GPIO88_F9") (pintype "bidirectional"))
    )
    (net (code "41") (name "AP4_SWDCLK") (class "Default")
      (node (ref "J1") (pin "4") (pinfunction "SWDCLK_4") (pintype "bidirectional"))
      (node (ref "J1") (pin "B4") (pinfunction "SWDCLK_B4") (pintype "bidirectional"))
      (node (ref "U1") (pin "K3") (pinfunction "GPIO20_K3") (pintype "bidirectional"))
    )
    (net (code "42") (name "AP4_SWDIO") (class "Default")
      (node (ref "J1") (pin "2") (pinfunction "SWDIO_2") (pintype "bidirectional"))
      (node (ref "J1") (pin "B2") (pinfunction "SWDIO_B2") (pintype "bidirectional"))
      (node (ref "U1") (pin "J3") (pinfunction "GPIO21_J3") (pintype "bidirectional"))
    )
    (net (code "43") (name "AP4_SWO") (class "Default")
      (node (ref "J1") (pin "6") (pinfunction "SWO_6") (pintype "bidirectional"))
      (node (ref "J1") (pin "B6") (pinfunction "SWO_B6") (pintype "bidirectional"))
      (node (ref "U1") (pin "L4") (pinfunction "GPIO3_L4") (pintype "bidirectional"))
    )
    (net (code "44") (name "AP4_USB0_N") (class "Default")
      (node (ref "D5") (pin "3") (pinfunction "I/O2_3") (pintype "bidirectional"))
      (node (ref "J7") (pin "A7") (pinfunction "DN1_A7") (pintype "bidirectional"))
      (node (ref "J7") (pin "B7") (pinfunction "DN2_B7") (pintype "bidirectional"))
      (node (ref "U1") (pin "M8") (pinfunction "USB0PN_M8") (pintype "bidirectional"))
    )
    (net (code "45") (name "AP4_USB0_P") (class "Default")
      (node (ref "D5") (pin "2") (pinfunction "I/O1_2") (pintype "bidirectional"))
      (node (ref "J7") (pin "A6") (pinfunction "DP1_A6") (pintype "bidirectional"))
      (node (ref "J7") (pin "B6") (pinfunction "DP2_B6") (pintype "bidirectional"))
      (node (ref "U1") (pin "M7") (pinfunction "USB0PP_M7") (pintype "bidirectional"))
    )
    (net (code "46") (name "AP4_VDDBH") (class "Default")
      (node (ref "C69") (pin "1") (pinfunction "1_1") (pintype "bidirectional"))
      (node (ref "L6") (pin "2") (pinfunction "2_2") (pintype "bidirectional"))
      (node (ref "RZ6") (pin "1") (pinfunction "1_1") (pintype "passive"))
      (node (ref "TP8") (pin "P$1") (pinfunction "TESTPOINT_P$1") (pintype "bidirectional"))
      (node (ref "U1") (pin "G12") (pinfunction "VDDBH--BLE_BUCK_VOUT_G12") (pintype "bidirectional"))
    )
    (net (code "47") (name "AP4_VDDBH_RF") (class "Default")
      (node (ref "C93") (pin "P$1") (pinfunction "1_P$1") (pintype "bidirectional"))
      (node (ref "RZ6") (pin "2") (pinfunction "2_2") (pintype "passive"))
      (node (ref "U1") (pin "J1") (pinfunction "VDDBH_RF--BLE_BUCK_RF_VOUT_J1") (pintype "bidirectional"))
    )
    (net (code "48") (name "AP4_VDDF") (class "Default")
      (node (ref "C61") (pin "P$1") (pinfunction "1_P$1") (pintype "bidirectional"))
      (node (ref "C75") (pin "P$1") (pinfunction "1_P$1") (pintype "bidirectional"))
      (node (ref "TP10") (pin "P$1") (pinfunction "TESTPOINT_P$1") (pintype "bidirectional"))
      (node (ref "U1") (pin "C2") (pinfunction "VDDF-MEM_C2") (pintype "bidirectional"))
    )
    (net (code "49") (name "AP4_VDDMIPI_1P8") (class "Default")
      (node (ref "C70") (pin "P$1") (pinfunction "1_P$1") (pintype "bidirectional"))
      (node (ref "SJ7") (pin "1") (pinfunction "1_1") (pintype "passive"))
      (node (ref "U1") (pin "H10") (pinfunction "VDD18-MIPI_H10") (pintype "bidirectional"))
    )
    (net (code "50") (name "AP4_VDDUSB_0P9") (class "Default")
      (node (ref "C73") (pin "P$1") (pinfunction "1_P$1") (pintype "bidirectional"))
      (node (ref "RZ3") (pin "2") (pinfunction "2_2") (pintype "passive"))
      (node (ref "U1") (pin "L7") (pinfunction "VDDUSB0P9_L7") (pintype "bidirectional"))
    )
    (net (code "51") (name "AP4_VDDUSB_3P3") (class "Default")
      (node (ref "C74") (pin "P$1") (pinfunction "1_P$1") (pintype "bidirectional"))
      (node (ref "RZ5") (pin "2") (pinfunction "2_2") (pintype "passive"))
      (node (ref "U1") (pin "K7") (pinfunction "VDDUSB33_K7") (pintype "bidirectional"))
    )
    (net (code "52") (name "AP4_~{RESET}") (class "Default")
      (node (ref "C76") (pin "1") (pinfunction "1_1") (pintype "passive"))
      (node (ref "D3") (pin "1") (pinfunction "C_1") (pintype "passive"))
      (node (ref "J1") (pin "3") (pinfunction "~{RESET}_3") (pintype "bidirectional"))
      (node (ref "J1") (pin "B3") (pinfunction "~{RESET}_B3") (pintype "bidirectional"))
      (node (ref "U1") (pin "A6") (pinfunction "~{RST}_A6") (pintype "input"))
    )
    (net (code "53") (name "BATT_THERM") (class "Default")
      (node (ref "J4") (pin "2") (pinfunction "2_2") (pintype "bidirectional"))
      (node (ref "J4") (pin "2SUPP") (pinfunction "2_2SUPP") (pintype "bidirectional"))
      (node (ref "SJ1") (pin "3") (pinfunction "3_3") (pintype "passive"))
    )
    (net (code "54") (name "BATT_TS") (class "Default")
      (node (ref "SJ1") (pin "2") (pinfunction "2_2") (pintype "passive"))
      (node (ref "U3") (pin "9") (pinfunction "TS_9") (pintype "bidirectional"))
    )
    (net (code "55") (name "BNO_ENV_SCL") (class "Default")
      (node (ref "R15") (pin "1") (pinfunction "1_1") (pintype "passive"))
      (node (ref "U6") (pin "15") (pinfunction "ENV_SCL_15") (pintype "bidirectional"))
    )
    (net (code "56") (name "BNO_ENV_SDA") (class "Default")
      (node (ref "R16") (pin "1") (pinfunction "1_1") (pintype "passive"))
      (node (ref "U6") (pin "16") (pinfunction "ENV_SDA_16") (pintype "bidirectional"))
    )
    (net (code "57") (name "DW_EXTON") (class "Default")
      (node (ref "S3") (pin "2") (pinfunction "CTL_2") (pintype "bidirectional"))
      (node (ref "S3") (pin "3") (pinfunction "CTL_3") (pintype "bidirectional"))
      (node (ref "SJ2") (pin "2") (pinfunction "2_2") (pintype "passive"))
      (node (ref "VR3") (pin "3") (pinfunction "EN_3") (pintype "input"))
    )
    (net (code "58") (name "DW_EXTON_RAW") (class "Default")
      (node (ref "SJ2") (pin "3") (pinfunction "3_3") (pintype "passive"))
      (node (ref "U2") (pin "A12") (pinfunction "EXTON_A12") (pintype "bidirectional"))
    )
    (net (code "59") (name "DW_GPIO6{slash}EXTRXE") (class "Default")
      (node (ref "SJ3") (pin "3") (pinfunction "3_3") (pintype "passive"))
      (node (ref "TP6") (pin "P$1") (pinfunction "TESTPOINT_P$1") (pintype "bidirectional"))
      (node (ref "U2") (pin "C4") (pinfunction "GPIO6/EXTRXE/SPIPHA_C4") (pintype "bidirectional"))
    )
    (net (code "60") (name "DW_RF1_BLKD") (class "Default")
      (node (ref "C2") (pin "P$2") (pinfunction "2_P$2") (pintype "bidirectional"))
      (node (ref "U7") (pin "6") (pinfunction "LNA_OUT_6") (pintype "bidirectional"))
    )
    (net (code "61") (name "DW_SYNC") (class "Default")
      (node (ref "TP7") (pin "P$1") (pinfunction "TESTPOINT_P$1") (pintype "bidirectional"))
      (node (ref "U2") (pin "G2") (pinfunction "GPIO7/SYNC_G2") (pintype "bidirectional"))
    )
    (net (code "62") (name "DW_VDD2_SUP") (class "Default")
      (node (ref "C13") (pin "P$1") (pinfunction "P$1_P$1") (pintype "bidirectional"))
      (node (ref "C24") (pin "P$1") (pinfunction "P$1_P$1") (pintype "bidirectional"))
      (node (ref "C55") (pin "P$1") (pinfunction "P$1_P$1") (pintype "bidirectional"))
      (node (ref "FB1") (pin "P$1") (pinfunction "P$1_P$1") (pintype "bidirectional"))
      (node (ref "RZ1") (pin "2") (pinfunction "2_2") (pintype "passive"))
      (node (ref "U2") (pin "B15") (pinfunction "VDD2B_B15") (pintype "bidirectional"))
    )
    (net (code "63") (name "DW_VDD3_SUP") (class "Default")
      (node (ref "C14") (pin "P$2") (pinfunction "P$2_P$2") (pintype "bidirectional"))
      (node (ref "C22") (pin "P$2") (pinfunction "P$2_P$2") (pintype "bidirectional"))
      (node (ref "C54") (pin "P$2") (pinfunction "P$2_P$2") (pintype "bidirectional"))
      (node (ref "RZ2") (pin "2") (pinfunction "2_2") (pintype "passive"))
      (node (ref "U2") (pin "D15") (pinfunction "VDD3_D15") (pintype "bidirectional"))
    )
    (net (code "64") (name "GND") (class "Default")
      (node (ref "C11") (pin "P$2") (pinfunction "P$2_P$2") (pintype "bidirectional"))
      (node (ref "C12") (pin "P$2") (pinfunction "P$2_P$2") (pintype "bidirectional"))
      (node (ref "C13") (pin "P$2") (pinfunction "P$2_P$2") (pintype "bidirectional"))
      (node (ref "C14") (pin "P$1") (pinfunction "P$1_P$1") (pintype "bidirectional"))
      (node (ref "C22") (pin "P$1") (pinfunction "P$1_P$1") (pintype "bidirectional"))
      (node (ref "C23") (pin "2") (pinfunction "2_2") (pintype "bidirectional"))
      (node (ref "C24") (pin "P$2") (pinfunction "P$2_P$2") (pintype "bidirectional"))
      (node (ref "C25") (pin "2") (pinfunction "2_2") (pintype "bidirectional"))
      (node (ref "C26") (pin "2") (pinfunction "2_2") (pintype "bidirectional"))
      (node (ref "C27") (pin "2") (pinfunction "2_2") (pintype "bidirectional"))
      (node (ref "C28") (pin "2") (pinfunction "2_2") (pintype "bidirectional"))
      (node (ref "C29") (pin "2") (pinfunction "2_2") (pintype "bidirectional"))
      (node (ref "C3") (pin "P$2") (pinfunction "P$2_P$2") (pintype "bidirectional"))
      (node (ref "C30") (pin "2") (pinfunction "2_2") (pintype "bidirectional"))
      (node (ref "C31") (pin "2") (pinfunction "2_2") (pintype "bidirectional"))
      (node (ref "C32") (pin "2") (pinfunction "2_2") (pintype "bidirectional"))
      (node (ref "C33") (pin "2") (pinfunction "2_2") (pintype "bidirectional"))
      (node (ref "C34") (pin "2") (pinfunction "2_2") (pintype "bidirectional"))
      (node (ref "C35") (pin "2") (pinfunction "2_2") (pintype "bidirectional"))
      (node (ref "C36") (pin "2") (pinfunction "2_2") (pintype "bidirectional"))
      (node (ref "C37") (pin "P$1") (pinfunction "P$1_P$1") (pintype "bidirectional"))
      (node (ref "C4") (pin "P$2") (pinfunction "P$2_P$2") (pintype "bidirectional"))
      (node (ref "C40") (pin "1") (pinfunction "1_1") (pintype "bidirectional"))
      (node (ref "C41") (pin "2") (pinfunction "2_2") (pintype "bidirectional"))
      (node (ref "C42") (pin "2") (pinfunction "2_2") (pintype "bidirectional"))
      (node (ref "C43") (pin "P$2") (pinfunction "P$2_P$2") (pintype "bidirectional"))
      (node (ref "C44") (pin "2") (pinfunction "2_2") (pintype "bidirectional"))
      (node (ref "C45") (pin "1") (pinfunction "1_1") (pintype "bidirectional"))
      (node (ref "C46") (pin "2") (pinfunction "2_2") (pintype "bidirectional"))
      (node (ref "C47") (pin "1") (pinfunction "1_1") (pintype "bidirectional"))
      (node (ref "C48") (pin "2") (pinfunction "2_2") (pintype "bidirectional"))
      (node (ref "C49") (pin "2") (pinfunction "2_2") (pintype "bidirectional"))
      (node (ref "C5") (pin "P$1") (pinfunction "1_P$1") (pintype "bidirectional"))
      (node (ref "C50") (pin "1") (pinfunction "1_1") (pintype "bidirectional"))
      (node (ref "C51") (pin "P$2") (pinfunction "2_P$2") (pintype "bidirectional"))
      (node (ref "C52") (pin "P$2") (pinfunction "2_P$2") (pintype "bidirectional"))
      (node (ref "C53") (pin "2") (pinfunction "2_2") (pintype "bidirectional"))
      (node (ref "C54") (pin "P$1") (pinfunction "P$1_P$1") (pintype "bidirectional"))
      (node (ref "C55") (pin "P$2") (pinfunction "P$2_P$2") (pintype "bidirectional"))
      (node (ref "C56") (pin "2") (pinfunction "2_2") (pintype "bidirectional"))
      (node (ref "C57") (pin "2") (pinfunction "2_2") (pintype "bidirectional"))
      (node (ref "C58") (pin "P$2") (pinfunction "2_P$2") (pintype "bidirectional"))
      (node (ref "C59") (pin "P$2") (pinfunction "2_P$2") (pintype "bidirectional"))
      (node (ref "C6") (pin "P$1") (pinfunction "1_P$1") (pintype "bidirectional"))
      (node (ref "C60") (pin "P$2") (pinfunction "2_P$2") (pintype "bidirectional"))
      (node (ref "C61") (pin "P$2") (pinfunction "2_P$2") (pintype "bidirectional"))
      (node (ref "C62") (pin "P$2") (pinfunction "2_P$2") (pintype "bidirectional"))
      (node (ref "C63") (pin "P$2") (pinfunction "2_P$2") (pintype "bidirectional"))
      (node (ref "C64") (pin "P$2") (pinfunction "2_P$2") (pintype "bidirectional"))
      (node (ref "C65") (pin "P$2") (pinfunction "2_P$2") (pintype "bidirectional"))
      (node (ref "C66") (pin "P$2") (pinfunction "2_P$2") (pintype "bidirectional"))
      (node (ref "C67") (pin "P$2") (pinfunction "2_P$2") (pintype "bidirectional"))
      (node (ref "C68") (pin "P$2") (pinfunction "2_P$2") (pintype "bidirectional"))
      (node (ref "C69") (pin "2") (pinfunction "2_2") (pintype "bidirectional"))
      (node (ref "C70") (pin "P$2") (pinfunction "2_P$2") (pintype "bidirectional"))
      (node (ref "C71") (pin "P$1") (pinfunction "1_P$1") (pintype "bidirectional"))
      (node (ref "C72") (pin "P$2") (pinfunction "2_P$2") (pintype "bidirectional"))
      (node (ref "C73") (pin "P$2") (pinfunction "2_P$2") (pintype "bidirectional"))
      (node (ref "C74") (pin "P$2") (pinfunction "2_P$2") (pintype "bidirectional"))
      (node (ref "C76") (pin "2") (pinfunction "2_2") (pintype "passive"))
      (node (ref "C77") (pin "P$2") (pinfunction "2_P$2") (pintype "bidirectional"))
      (node (ref "C78") (pin "P$2") (pinfunction "2_P$2") (pintype "bidirectional"))
      (node (ref "C79") (pin "P$1") (pinfunction "1_P$1") (pintype "bidirectional"))
      (node (ref "C80") (pin "2") (pinfunction "2_2") (pintype "passive"))
      (node (ref "C81") (pin "2") (pinfunction "2_2") (pintype "passive"))
      (node (ref "C82") (pin "P$2") (pinfunction "2_P$2") (pintype "bidirectional"))
      (node (ref "C90") (pin "P$2") (pinfunction "2_P$2") (pintype "bidirectional"))
      (node (ref "C91") (pin "P$2") (pinfunction "2_P$2") (pintype "bidirectional"))
      (node (ref "CX1") (pin "2") (pinfunction "2_2") (pintype "passive"))
      (node (ref "CX2") (pin "2") (pinfunction "2_2") (pintype "passive"))
      (node (ref "D3") (pin "2") (pinfunction "A_2") (pintype "passive"))
      (node (ref "D5") (pin "1") (pinfunction "GND_1") (pintype "bidirectional"))
      (node (ref "J1") (pin "5") (pinfunction "GND_5") (pintype "bidirectional"))
      (node (ref "J1") (pin "B5") (pinfunction "GND_B5") (pintype "bidirectional"))
      (node (ref "J3") (pin "2") (pinfunction "2_2") (pintype "passive"))
      (node (ref "J4") (pin "1") (pinfunction "1_1") (pintype "bidirectional"))
      (node (ref "J4") (pin "1SUPP") (pinfunction "1_1SUPP") (pintype "bidirectional"))
      (node (ref "J7") (pin "A1/B12") (pinfunction "GND_A1/B12") (pintype "power_in"))
      (node (ref "J7") (pin "B1/A12") (pinfunction "GND_B1/A12") (pintype "power_in"))
      (node (ref "J7") (pin "S1") (pinfunction "GND_S1") (pintype "power_in"))
      (node (ref "J7") (pin "S2") (pinfunction "GND_S2") (pintype "power_in"))
      (node (ref "J7") (pin "S3") (pinfunction "GND_S3") (pintype "power_in"))
      (node (ref "J7") (pin "S4") (pinfunction "GND_S4") (pintype "power_in"))
      (node (ref "Q2") (pin "S") (pinfunction "S_S") (pintype "passive"))
      (node (ref "R1") (pin "2") (pinfunction "2_2") (pintype "passive"))
      (node (ref "R10") (pin "1") (pinfunction "1_1") (pintype "passive"))
      (node (ref "R11") (pin "1") (pinfunction "1_1") (pintype "passive"))
      (node (ref "R12") (pin "2") (pinfunction "2_2") (pintype "passive"))
      (node (ref "R13") (pin "2") (pinfunction "2_2") (pintype "passive"))
      (node (ref "R19") (pin "1") (pinfunction "1_1") (pintype "passive"))
      (node (ref "R20") (pin "2") (pinfunction "2_2") (pintype "passive"))
      (node (ref "R21") (pin "1") (pinfunction "1_1") (pintype "passive"))
      (node (ref "R22") (pin "1") (pinfunction "1_1") (pintype "passive"))
      (node (ref "R23") (pin "1") (pinfunction "1_1") (pintype "passive"))
      (node (ref "R27") (pin "1") (pinfunction "1_1") (pintype "passive"))
      (node (ref "R6") (pin "2") (pinfunction "2_2") (pintype "passive"))
      (node (ref "RX1") (pin "1") (pinfunction "1_1") (pintype "passive"))
      (node (ref "RX2") (pin "1") (pinfunction "1_1") (pintype "passive"))
      (node (ref "S2") (pin "10") (pinfunction "GND_10") (pintype "bidirectional"))
      (node (ref "S2") (pin "12") (pinfunction "GND_12") (pintype "bidirectional"))
      (node (ref "S2") (pin "2") (pinfunction "GND_2") (pintype "bidirectional"))
      (node (ref "S2") (pin "7") (pinfunction "GND_7") (pintype "bidirectional"))
      (node (ref "S2") (pin "8") (pinfunction "GND_8") (pintype "bidirectional"))
      (node (ref "S2") (pin "PAD") (pinfunction "GND_PAD") (pintype "bidirectional"))
      (node (ref "S3") (pin "6") (pinfunction "GND_6") (pintype "bidirectional"))
      (node (ref "S3") (pin "7") (pinfunction "GND_7") (pintype "bidirectional"))
      (node (ref "S3") (pin "PAD") (pinfunction "GND_PAD") (pintype "bidirectional"))
      (node (ref "SJ3") (pin "1") (pinfunction "1_1") (pintype "passive"))
      (node (ref "SJ4") (pin "1") (pinfunction "1_1") (pintype "passive"))
      (node (ref "SJ7") (pin "2") (pinfunction "2_2") (pintype "passive"))
      (node (ref "U1") (pin "B12") (pinfunction "VSSAUDA_B12") (pintype "bidirectional"))
      (node (ref "U1") (pin "B2") (pinfunction "VSSP-BUCK_REGS_GND_B2") (pintype "bidirectional"))
      (node (ref "U1") (pin "B5") (pinfunction "VSSA-ANALOG_GND_B5") (pintype "bidirectional"))
      (node (ref "U1") (pin "D2") (pinfunction "VSS-DGND_FOR_VDDF_AND_PADS_D2") (pintype "bidirectional"))
      (node (ref "U1") (pin "E12") (pinfunction "VSSAUDD_E12") (pintype "bidirectional"))
      (node (ref "U1") (pin "H1") (pinfunction "VSSB-BLE_UNREG_GND_H1") (pintype "bidirectional"))
      (node (ref "U1") (pin "J10") (pinfunction "VSS18-MIPI_J10") (pintype "bidirectional"))
      (node (ref "U1") (pin "L1") (pinfunction "VSSVCO-BLECORE_GND_FOR_VCO_L1") (pintype "bidirectional"))
      (node (ref "U1") (pin "L2") (pinfunction "VSSS-HVSIMOBUCK_GND_L2") (pintype "bidirectional"))
      (node (ref "U1") (pin "L8") (pinfunction "VSSAUSB_L8") (pintype "bidirectional"))
      (node (ref "U2") (pin "A14") (pinfunction "VSS1_A14") (pintype "bidirectional"))
      (node (ref "U2") (pin "A2") (pinfunction "VSS_A2") (pintype "bidirectional"))
      (node (ref "U2") (pin "B11") (pinfunction "VSS1_B11") (pintype "bidirectional"))
      (node (ref "U2") (pin "B3") (pinfunction "VSS_B3") (pintype "bidirectional"))
      (node (ref "U2") (pin "C10") (pinfunction "VSS1_C10") (pintype "bidirectional"))
      (node (ref "U2") (pin "C12") (pinfunction "VSS3_C12") (pintype "bidirectional"))
      (node (ref "U2") (pin "C6") (pinfunction "VSS_C6") (pintype "bidirectional"))
      (node (ref "U2") (pin "C8") (pinfunction "VSS1_C8") (pintype "bidirectional"))
      (node (ref "U2") (pin "D11") (pinfunction "VSS2_D11") (pintype "bidirectional"))
      (node (ref "U2") (pin "D13") (pinfunction "VSS3_D13") (pintype "bidirectional"))
      (node (ref "U2") (pin "D5") (pinfunction "VSS_D5") (pintype "bidirectional"))
      (node (ref "U2") (pin "D7") (pinfunction "VSS_D7") (pintype "bidirectional"))
      (node (ref "U2") (pin "D9") (pinfunction "VSS1_D9") (pintype "bidirectional"))
      (node (ref "U2") (pin "E10") (pinfunction "GND-RF_E10") (pintype "bidirectional"))
      (node (ref "U2") (pin "E12") (pinfunction "GND-RF_E12") (pintype "bidirectional"))
      (node (ref "U2") (pin "E14") (pinfunction "VSS2_E14") (pintype "bidirectional"))
      (node (ref "U2") (pin "E6") (pinfunction "GND-RF_E6") (pintype "bidirectional"))
      (node (ref "U2") (pin "F7") (pinfunction "GND-RF_F7") (pintype "bidirectional"))
      (node (ref "U2") (pin "F9") (pinfunction "GND-RF_F9") (pintype "bidirectional"))
      (node (ref "U2") (pin "G10") (pinfunction "GND-RF_G10") (pintype "bidirectional"))
      (node (ref "U2") (pin "G6") (pinfunction "GND-RF_G6") (pintype "bidirectional"))
      (node (ref "U2") (pin "H1") (pinfunction "GND-RF_H1") (pintype "bidirectional"))
      (node (ref "U2") (pin "H13") (pinfunction "GND-RF_H13") (pintype "bidirectional"))
      (node (ref "U2") (pin "H3") (pinfunction "GND-RF_H3") (pintype "bidirectional"))
      (node (ref "U2") (pin "H7") (pinfunction "GND-RF_H7") (pintype "bidirectional"))
      (node (ref "U2") (pin "H9") (pinfunction "GND-RF_H9") (pintype "bidirectional"))
      (node (ref "U3") (pin "3") (pinfunction "VSS_3") (pintype "bidirectional"))
      (node (ref "U3") (pin "7") (pinfunction "ISET2_7") (pintype "bidirectional"))
      (node (ref "U3") (pin "PAD") (pinfunction "VSS_PAD") (pintype "bidirectional"))
      (node (ref "U4") (pin "1") (pinfunction "PGND_1") (pintype "bidirectional"))
      (node (ref "U4") (pin "10") (pinfunction "EN1_10") (pintype "bidirectional"))
      (node (ref "U4") (pin "11") (pinfunction "EN2_11") (pintype "bidirectional"))
      (node (ref "U4") (pin "20") (pinfunction "PGND_20") (pintype "bidirectional"))
      (node (ref "U4") (pin "PAD") (pinfunction "PGND_PAD") (pintype "bidirectional"))
      (node (ref "U6") (pin "10") (pinfunction "CLKSEL0_10") (pintype "output"))
      (node (ref "U6") (pin "2") (pinfunction "GND_2") (pintype "bidirectional"))
      (node (ref "U6") (pin "25") (pinfunction "GNDIO_25") (pintype "bidirectional"))
      (node (ref "U7") (pin "3") (pinfunction "GND_3") (pintype "bidirectional"))
      (node (ref "U7") (pin "4") (pinfunction "GND_4") (pintype "bidirectional"))
      (node (ref "U7") (pin "5") (pinfunction "GND_5") (pintype "bidirectional"))
      (node (ref "U7") (pin "7") (pinfunction "GND_7") (pintype "bidirectional"))
      (node (ref "U7") (pin "9") (pinfunction "GND_9") (pintype "bidirectional"))
      (node (ref "U8") (pin "4") (pinfunction "GND_4") (pintype "bidirectional"))
      (node (ref "VR1") (pin "13") (pinfunction "GND2_13") (pintype "bidirectional"))
      (node (ref "VR1") (pin "3") (pinfunction "GND2_3") (pintype "bidirectional"))
      (node (ref "VR1") (pin "9") (pinfunction "GND1_9") (pintype "bidirectional"))
      (node (ref "VR2") (pin "2") (pinfunction "GND_2") (pintype "bidirectional"))
      (node (ref "VR2") (pin "PAD") (pinfunction "GND_PAD") (pintype "bidirectional"))
      (node (ref "VR3") (pin "2") (pinfunction "GND_2") (pintype "bidirectional"))
      (node (ref "VR3") (pin "PAD") (pinfunction "GND_PAD") (pintype "bidirectional"))
      (node (ref "VR4") (pin "2") (pinfunction "GND_2") (pintype "bidirectional"))
      (node (ref "VR4") (pin "PAD") (pinfunction "GND_PAD") (pintype "bidirectional"))
      (node (ref "VR5") (pin "2") (pinfunction "GND_2") (pintype "bidirectional"))
      (node (ref "X1") (pin "2") (pinfunction "GND_2") (pintype "bidirectional"))
      (node (ref "X1") (pin "4") (pinfunction "GND_4") (pintype "bidirectional"))
      (node (ref "X4") (pin "2") (pinfunction "GND_2") (pintype "bidirectional"))
      (node (ref "X4") (pin "4") (pinfunction "GND_4") (pintype "bidirectional"))
    )
    (net (code "65") (name "Net-(A4-ANTENNA)") (class "Default")
      (node (ref "A4") (pin "S1") (pinfunction "ANTENNA_S1") (pintype "bidirectional"))
      (node (ref "L8") (pin "2") (pinfunction "2_2") (pintype "passive"))
    )
    (net (code "66") (name "Net-(C1-Pad1)") (class "Default")
      (node (ref "C1") (pin "1") (pinfunction "1_1") (pintype "passive"))
      (node (ref "L7") (pin "2") (pinfunction "2_2") (pintype "passive"))
      (node (ref "L8") (pin "1") (pinfunction "1_1") (pintype "passive"))
    )
    (net (code "67") (name "Net-(C2-1)") (class "Default")
      (node (ref "C2") (pin "P$1") (pinfunction "1_P$1") (pintype "bidirectional"))
      (node (ref "U2") (pin "H11") (pinfunction "RF1_H11") (pintype "bidirectional"))
    )
    (net (code "68") (name "Net-(C5-2)") (class "Default")
      (node (ref "C5") (pin "P$2") (pinfunction "2_P$2") (pintype "bidirectional"))
      (node (ref "U6") (pin "27") (pinfunction "XIN32_27") (pintype "bidirectional"))
      (node (ref "X2") (pin "2") (pinfunction "2_2") (pintype "bidirectional"))
    )
    (net (code "69") (name "Net-(C6-2)") (class "Default")
      (node (ref "C6") (pin "P$2") (pinfunction "2_P$2") (pintype "bidirectional"))
      (node (ref "U6") (pin "26") (pinfunction "XOUT32/CLKSEL1_26") (pintype "bidirectional"))
      (node (ref "X2") (pin "1") (pinfunction "1_1") (pintype "bidirectional"))
    )
    (net (code "70") (name "Net-(C7-2)") (class "Default")
      (node (ref "C7") (pin "P$2") (pinfunction "2_P$2") (pintype "bidirectional"))
      (node (ref "R21") (pin "2") (pinfunction "2_2") (pintype "passive"))
      (node (ref "R24") (pin "1") (pinfunction "1_1") (pintype "passive"))
      (node (ref "VR1") (pin "10") (pinfunction "FB2_10") (pintype "bidirectional"))
    )
    (net (code "71") (name "Net-(C8-1)") (class "Default")
      (node (ref "C8") (pin "P$1") (pinfunction "1_P$1") (pintype "bidirectional"))
      (node (ref "R22") (pin "2") (pinfunction "2_2") (pintype "passive"))
      (node (ref "R25") (pin "2") (pinfunction "2_2") (pintype "passive"))
      (node (ref "VR1") (pin "4") (pinfunction "FB1_4") (pintype "bidirectional"))
    )
    (net (code "72") (name "Net-(C52-1)") (class "Default")
      (node (ref "C52") (pin "P$1") (pinfunction "1_P$1") (pintype "bidirectional"))
      (node (ref "RZ3") (pin "1") (pinfunction "1_1") (pintype "passive"))
      (node (ref "VR5") (pin "5") (pinfunction "OUT_5") (pintype "power_in"))
    )
    (net (code "73") (name "Net-(C58-1)") (class "Default")
      (node (ref "C58") (pin "P$1") (pinfunction "1_P$1") (pintype "bidirectional"))
      (node (ref "U1") (pin "C1") (pinfunction "VDDS-SRAM_HV_SUP_C1") (pintype "bidirectional"))
    )
    (net (code "74") (name "Net-(C59-1)") (class "Default")
      (node (ref "C59") (pin "P$1") (pinfunction "1_P$1") (pintype "bidirectional"))
      (node (ref "U1") (pin "A3") (pinfunction "VDDC-CORE_A3") (pintype "bidirectional"))
    )
    (net (code "75") (name "Net-(C60-1)") (class "Default")
      (node (ref "C60") (pin "P$1") (pinfunction "1_P$1") (pintype "bidirectional"))
      (node (ref "U1") (pin "B3") (pinfunction "VDDC_LV-CORE_LV_B3") (pintype "bidirectional"))
    )
    (net (code "76") (name "Net-(C71-2)") (class "Default")
      (node (ref "C71") (pin "P$2") (pinfunction "2_P$2") (pintype "bidirectional"))
      (node (ref "U1") (pin "B10") (pinfunction "LPMICBIAS_B10") (pintype "output"))
    )
    (net (code "77") (name "Net-(C79-2)") (class "Default")
      (node (ref "C79") (pin "P$2") (pinfunction "2_P$2") (pintype "bidirectional"))
      (node (ref "U1") (pin "A12") (pinfunction "LPADC_VREF_A12") (pintype "bidirectional"))
    )
    (net (code "78") (name "Net-(C82-1)") (class "Default")
      (node (ref "C82") (pin "P$1") (pinfunction "1_P$1") (pintype "bidirectional"))
      (node (ref "RZ5") (pin "1") (pinfunction "1_1") (pintype "passive"))
      (node (ref "VR4") (pin "1") (pinfunction "OUT_1") (pintype "power_in"))
    )
    (net (code "79") (name "Net-(C91-1)") (class "Default")
      (node (ref "C91") (pin "P$1") (pinfunction "1_P$1") (pintype "bidirectional"))
      (node (ref "RZ4") (pin "1") (pinfunction "1_1") (pintype "passive"))
      (node (ref "VR3") (pin "1") (pinfunction "OUT_1") (pintype "power_in"))
    )
    (net (code "80") (name "Net-(D1-PadC1)") (class "Default")
      (node (ref "D1") (pin "C1") (pinfunction "C1_C1") (pintype "bidirectional"))
      (node (ref "R5") (pin "1") (pinfunction "1_1") (pintype "passive"))
    )
    (net (code "81") (name "Net-(D1-PadC2)") (class "Default")
      (node (ref "D1") (pin "C2") (pinfunction "C2_C2") (pintype "bidirectional"))
      (node (ref "R2") (pin "1") (pinfunction "1_1") (pintype "passive"))
    )
    (net (code "82") (name "Net-(D2-PadC1)") (class "Default")
      (node (ref "D2") (pin "C1") (pinfunction "C1_C1") (pintype "bidirectional"))
      (node (ref "R4") (pin "1") (pinfunction "1_1") (pintype "passive"))
    )
    (net (code "83") (name "Net-(D2-PadC2)") (class "Default")
      (node (ref "D2") (pin "C2") (pinfunction "C2_C2") (pintype "bidirectional"))
      (node (ref "R3") (pin "1") (pinfunction "1_1") (pintype "passive"))
    )
    (net (code "84") (name "Net-(J7-CC1)") (class "Default")
      (node (ref "J7") (pin "A5") (pinfunction "CC1_A5") (pintype "bidirectional"))
      (node (ref "R12") (pin "1") (pinfunction "1_1") (pintype "passive"))
    )
    (net (code "85") (name "Net-(J7-CC2)") (class "Default")
      (node (ref "J7") (pin "B5") (pinfunction "CC2_B5") (pintype "bidirectional"))
      (node (ref "R13") (pin "1") (pinfunction "1_1") (pintype "passive"))
    )
    (net (code "86") (name "Net-(L1-1)") (class "Default")
      (node (ref "L1") (pin "P$1") (pinfunction "1_P$1") (pintype "bidirectional"))
      (node (ref "VR1") (pin "2") (pinfunction "LX2_2") (pintype "bidirectional"))
    )
    (net (code "87") (name "Net-(L2-2)") (class "Default")
      (node (ref "L2") (pin "P$2") (pinfunction "2_P$2") (pintype "bidirectional"))
      (node (ref "VR1") (pin "8") (pinfunction "LX1_8") (pintype "bidirectional"))
    )
    (net (code "88") (name "Net-(L4-1)") (class "Default")
      (node (ref "C17") (pin "2") (pinfunction "2_2") (pintype "bidirectional"))
      (node (ref "C18") (pin "2") (pinfunction "2_2") (pintype "bidirectional"))
      (node (ref "C19") (pin "2") (pinfunction "2_2") (pintype "bidirectional"))
      (node (ref "L4") (pin "P$1") (pinfunction "1_P$1") (pintype "bidirectional"))
    )
    (net (code "89") (name "Net-(L4-2)") (class "Default")
      (node (ref "C10") (pin "2") (pinfunction "2_2") (pintype "bidirectional"))
      (node (ref "C16") (pin "2") (pinfunction "2_2") (pintype "bidirectional"))
      (node (ref "C21") (pin "2") (pinfunction "2_2") (pintype "bidirectional"))
      (node (ref "C39") (pin "2") (pinfunction "2_2") (pintype "bidirectional"))
      (node (ref "C9") (pin "2") (pinfunction "2_2") (pintype "bidirectional"))
      (node (ref "L4") (pin "P$2") (pinfunction "2_P$2") (pintype "bidirectional"))
      (node (ref "U4") (pin "19") (pinfunction "AC2_19") (pintype "bidirectional"))
    )
    (net (code "90") (name "Net-(L5-1)") (class "Default")
      (node (ref "L5") (pin "P$1") (pinfunction "1_P$1") (pintype "bidirectional"))
      (node (ref "U1") (pin "A1") (pinfunction "SIMOBUCK_SW_A1") (pintype "bidirectional"))
    )
    (net (code "91") (name "Net-(L5-2)") (class "Default")
      (node (ref "L5") (pin "P$2") (pinfunction "2_P$2") (pintype "bidirectional"))
      (node (ref "U1") (pin "A2") (pinfunction "SIMOBUCK_SWSEL_A2") (pintype "bidirectional"))
    )
    (net (code "92") (name "Net-(LS1-N)") (class "Default")
      (node (ref "D4") (pin "ANODE") (pinfunction "ANODE_ANODE") (pintype "bidirectional"))
      (node (ref "LS1") (pin "-") (pinfunction "N_-") (pintype "passive"))
      (node (ref "Q2") (pin "D") (pinfunction "D_D") (pintype "passive"))
    )
    (net (code "93") (name "Net-(R6-Pad1)") (class "Default")
      (node (ref "R6") (pin "1") (pinfunction "1_1") (pintype "passive"))
      (node (ref "R7") (pin "2") (pinfunction "2_2") (pintype "passive"))
    )
    (net (code "94") (name "Net-(R8-Pad2)") (class "Default")
      (node (ref "R8") (pin "2") (pinfunction "2_2") (pintype "passive"))
      (node (ref "R9") (pin "1") (pinfunction "1_1") (pintype "passive"))
    )
    (net (code "95") (name "Net-(R10-Pad2)") (class "Default")
      (node (ref "R10") (pin "2") (pinfunction "2_2") (pintype "passive"))
      (node (ref "RT1") (pin "1") (pinfunction "1_1") (pintype "passive"))
    )
    (net (code "96") (name "Net-(R17-Pad1)") (class "Default")
      (node (ref "R17") (pin "1") (pinfunction "1_1") (pintype "passive"))
      (node (ref "R18") (pin "2") (pinfunction "2_2") (pintype "passive"))
    )
    (net (code "97") (name "Net-(RX1-Pad2)") (class "Default")
      (node (ref "RX1") (pin "2") (pinfunction "2_2") (pintype "passive"))
      (node (ref "SJ1") (pin "1") (pinfunction "1_1") (pintype "passive"))
    )
    (net (code "98") (name "Net-(S3A-OUT)") (class "Default")
      (node (ref "C33") (pin "1") (pinfunction "1_1") (pintype "bidirectional"))
      (node (ref "RZ1") (pin "1") (pinfunction "1_1") (pintype "passive"))
      (node (ref "S3") (pin "8") (pinfunction "OUT_8") (pintype "bidirectional"))
    )
    (net (code "99") (name "Net-(S3B-OUT)") (class "Default")
      (node (ref "C25") (pin "1") (pinfunction "1_1") (pintype "bidirectional"))
      (node (ref "RZ2") (pin "1") (pinfunction "1_1") (pintype "passive"))
      (node (ref "S3") (pin "5") (pinfunction "OUT_5") (pintype "bidirectional"))
    )
    (net (code "100") (name "Net-(TP0-TESTPOINT)") (class "Default")
      (node (ref "TP0") (pin "P$1") (pinfunction "TESTPOINT_P$1") (pintype "bidirectional"))
      (node (ref "U2") (pin "C2") (pinfunction "GPIO0/RXOKLED_C2") (pintype "bidirectional"))
    )
    (net (code "101") (name "Net-(TP1-TESTPOINT)") (class "Default")
      (node (ref "TP1") (pin "P$1") (pinfunction "TESTPOINT_P$1") (pintype "bidirectional"))
      (node (ref "U2") (pin "D3") (pinfunction "GPIO1/SFDLED_D3") (pintype "bidirectional"))
    )
    (net (code "102") (name "Net-(TP2-TESTPOINT)") (class "Default")
      (node (ref "TP2") (pin "P$1") (pinfunction "TESTPOINT_P$1") (pintype "bidirectional"))
      (node (ref "U2") (pin "E4") (pinfunction "GPIO2/RXLED_E4") (pintype "bidirectional"))
    )
    (net (code "103") (name "Net-(TP3-TESTPOINT)") (class "Default")
      (node (ref "TP3") (pin "P$1") (pinfunction "TESTPOINT_P$1") (pintype "bidirectional"))
      (node (ref "U2") (pin "E2") (pinfunction "GPIO3/TXLED_E2") (pintype "bidirectional"))
    )
    (net (code "104") (name "Net-(TP4-TESTPOINT)") (class "Default")
      (node (ref "TP4") (pin "P$1") (pinfunction "TESTPOINT_P$1") (pintype "bidirectional"))
      (node (ref "U2") (pin "F1") (pinfunction "GPIO4/EXTPA_F1") (pintype "bidirectional"))
    )
    (net (code "105") (name "Net-(TP5-TESTPOINT)") (class "Default")
      (node (ref "TP5") (pin "P$1") (pinfunction "TESTPOINT_P$1") (pintype "bidirectional"))
      (node (ref "U2") (pin "D1") (pinfunction "GPIO5/EXTTXE/SPIPOL_D1") (pintype "bidirectional"))
    )
    (net (code "106") (name "Net-(U1-RFIOP)") (class "Default")
      (node (ref "L7") (pin "1") (pinfunction "1_1") (pintype "passive"))
      (node (ref "U1") (pin "M2") (pinfunction "RFIOP_M2") (pintype "bidirectional"))
    )
    (net (code "107") (name "Net-(U1-VDDBH_SW--BLE_BUCK_SW)") (class "Default")
      (node (ref "L6") (pin "1") (pinfunction "1_1") (pintype "bidirectional"))
      (node (ref "U1") (pin "H12") (pinfunction "VDDBH_SW--BLE_BUCK_SW_H12") (pintype "bidirectional"))
    )
    (net (code "108") (name "Net-(U1-XI)") (class "Default")
      (node (ref "C81") (pin "1") (pinfunction "1_1") (pintype "passive"))
      (node (ref "U1") (pin "A4") (pinfunction "XI_A4") (pintype "bidirectional"))
      (node (ref "X3") (pin "2") (pinfunction "2_2") (pintype "bidirectional"))
    )
    (net (code "109") (name "Net-(U1-XI32M)") (class "Default")
      (node (ref "CX2") (pin "1") (pinfunction "1_1") (pintype "passive"))
      (node (ref "U1") (pin "C12") (pinfunction "XI32M_C12") (pintype "bidirectional"))
      (node (ref "X1") (pin "3") (pinfunction "2_3") (pintype "bidirectional"))
    )
    (net (code "110") (name "Net-(U1-XO)") (class "Default")
      (node (ref "C80") (pin "1") (pinfunction "1_1") (pintype "passive"))
      (node (ref "U1") (pin "A5") (pinfunction "XO_A5") (pintype "bidirectional"))
      (node (ref "X3") (pin "1") (pinfunction "1_1") (pintype "bidirectional"))
    )
    (net (code "111") (name "Net-(U1-XO32M)") (class "Default")
      (node (ref "CX1") (pin "1") (pinfunction "1_1") (pintype "passive"))
      (node (ref "U1") (pin "D12") (pinfunction "XO32M_D12") (pintype "bidirectional"))
      (node (ref "X1") (pin "1") (pinfunction "1_1") (pintype "bidirectional"))
    )
    (net (code "112") (name "Net-(U2-RF2)") (class "Default")
      (node (ref "R1") (pin "1") (pinfunction "1_1") (pintype "passive"))
      (node (ref "U2") (pin "H5") (pinfunction "RF2_H5") (pintype "bidirectional"))
    )
    (net (code "113") (name "Net-(U2-VDD2A)") (class "Default")
      (node (ref "C12") (pin "P$1") (pinfunction "P$1_P$1") (pintype "bidirectional"))
      (node (ref "FB1") (pin "P$2") (pinfunction "P$2_P$2") (pintype "bidirectional"))
      (node (ref "U2") (pin "F15") (pinfunction "VDD2A_F15") (pintype "bidirectional"))
    )
    (net (code "114") (name "Net-(U2-VIO_D)") (class "Default")
      (node (ref "C23") (pin "1") (pinfunction "1_1") (pintype "bidirectional"))
      (node (ref "U2") (pin "A4") (pinfunction "VIO_D_A4") (pintype "bidirectional"))
    )
    (net (code "115") (name "Net-(U2-VTX_D)") (class "Default")
      (node (ref "C37") (pin "P$2") (pinfunction "P$2_P$2") (pintype "bidirectional"))
      (node (ref "U2") (pin "C14") (pinfunction "VTX_D_C14") (pintype "bidirectional"))
    )
    (net (code "116") (name "Net-(U2-XTI)") (class "Default")
      (node (ref "C3") (pin "P$1") (pinfunction "P$1_P$1") (pintype "bidirectional"))
      (node (ref "U2") (pin "H15") (pinfunction "XTI_H15") (pintype "bidirectional"))
      (node (ref "X4") (pin "1") (pinfunction "1_1") (pintype "bidirectional"))
    )
    (net (code "117") (name "Net-(U2-XTO)") (class "Default")
      (node (ref "C4") (pin "P$1") (pinfunction "P$1_P$1") (pintype "bidirectional"))
      (node (ref "U2") (pin "G14") (pinfunction "XTO_G14") (pintype "bidirectional"))
      (node (ref "X4") (pin "3") (pinfunction "2_3") (pintype "bidirectional"))
    )
    (net (code "118") (name "Net-(U3-ISET)") (class "Default")
      (node (ref "R11") (pin "2") (pinfunction "2_2") (pintype "passive"))
      (node (ref "U3") (pin "2") (pinfunction "ISET_2") (pintype "bidirectional"))
    )
    (net (code "119") (name "Net-(U3-PRETERM)") (class "Default")
      (node (ref "RX2") (pin "2") (pinfunction "2_2") (pintype "passive"))
      (node (ref "U3") (pin "4") (pinfunction "PRETERM_4") (pintype "bidirectional"))
    )
    (net (code "120") (name "Net-(U4-AC1)") (class "Default")
      (node (ref "C10") (pin "1") (pinfunction "1_1") (pintype "bidirectional"))
      (node (ref "C15") (pin "2") (pinfunction "2_2") (pintype "bidirectional"))
      (node (ref "C17") (pin "1") (pinfunction "1_1") (pintype "bidirectional"))
      (node (ref "C18") (pin "1") (pinfunction "1_1") (pintype "bidirectional"))
      (node (ref "C19") (pin "1") (pinfunction "1_1") (pintype "bidirectional"))
      (node (ref "C20") (pin "2") (pinfunction "2_2") (pintype "bidirectional"))
      (node (ref "C38") (pin "2") (pinfunction "2_2") (pintype "bidirectional"))
      (node (ref "C9") (pin "1") (pinfunction "1_1") (pintype "bidirectional"))
      (node (ref "U4") (pin "2") (pinfunction "AC1_2") (pintype "bidirectional"))
    )
    (net (code "121") (name "Net-(U4-BOOT1)") (class "Default")
      (node (ref "C15") (pin "1") (pinfunction "1_1") (pintype "bidirectional"))
      (node (ref "U4") (pin "3") (pinfunction "BOOT1_3") (pintype "bidirectional"))
    )
    (net (code "122") (name "Net-(U4-BOOT2)") (class "Default")
      (node (ref "C16") (pin "1") (pinfunction "1_1") (pintype "bidirectional"))
      (node (ref "U4") (pin "17") (pinfunction "BOOT2_17") (pintype "bidirectional"))
    )
    (net (code "123") (name "Net-(U4-CLAMP1)") (class "Default")
      (node (ref "C38") (pin "1") (pinfunction "1_1") (pintype "bidirectional"))
      (node (ref "U4") (pin "5") (pinfunction "CLAMP1_5") (pintype "bidirectional"))
    )
    (net (code "124") (name "Net-(U4-CLAMP2)") (class "Default")
      (node (ref "C39") (pin "1") (pinfunction "1_1") (pintype "bidirectional"))
      (node (ref "U4") (pin "16") (pinfunction "CLAMP2_16") (pintype "bidirectional"))
    )
    (net (code "125") (name "Net-(U4-COMM1)") (class "Default")
      (node (ref "C20") (pin "1") (pinfunction "1_1") (pintype "bidirectional"))
      (node (ref "U4") (pin "6") (pinfunction "COMM1_6") (pintype "bidirectional"))
    )
    (net (code "126") (name "Net-(U4-COMM2)") (class "Default")
      (node (ref "C21") (pin "1") (pinfunction "1_1") (pintype "bidirectional"))
      (node (ref "U4") (pin "15") (pinfunction "COMM2_15") (pintype "bidirectional"))
    )
    (net (code "127") (name "Net-(U4-FOD)") (class "Default")
      (node (ref "R17") (pin "2") (pinfunction "2_2") (pintype "passive"))
      (node (ref "R7") (pin "1") (pinfunction "1_1") (pintype "passive"))
      (node (ref "R9") (pin "2") (pinfunction "2_2") (pintype "passive"))
      (node (ref "U4") (pin "14") (pinfunction "FOD_14") (pintype "bidirectional"))
    )
    (net (code "128") (name "Net-(U4-ILIM)") (class "Default")
      (node (ref "R8") (pin "1") (pinfunction "1_1") (pintype "passive"))
      (node (ref "U4") (pin "12") (pinfunction "ILIM_12") (pintype "bidirectional"))
    )
    (net (code "129") (name "Net-(U4-RECT)") (class "Default")
      (node (ref "C28") (pin "1") (pinfunction "1_1") (pintype "bidirectional"))
      (node (ref "C56") (pin "1") (pinfunction "1_1") (pintype "bidirectional"))
      (node (ref "C57") (pin "1") (pinfunction "1_1") (pintype "bidirectional"))
      (node (ref "R18") (pin "1") (pinfunction "1_1") (pintype "passive"))
      (node (ref "U4") (pin "18") (pinfunction "RECT_18") (pintype "bidirectional"))
    )
    (net (code "130") (name "Net-(U6-CAP)") (class "Default")
      (node (ref "C36") (pin "1") (pinfunction "1_1") (pintype "bidirectional"))
      (node (ref "U6") (pin "9") (pinfunction "CAP_9") (pintype "bidirectional"))
    )
    (net (code "131") (name "Net-(U6-PS1)") (class "Default")
      (node (ref "SJ4") (pin "2") (pinfunction "2_2") (pintype "passive"))
      (node (ref "U6") (pin "5") (pinfunction "PS1_5") (pintype "input"))
    )
    (net (code "132") (name "Net-(U7-VCTRL)") (class "Default")
      (node (ref "SJ3") (pin "2") (pinfunction "2_2") (pintype "passive"))
      (node (ref "U7") (pin "8") (pinfunction "VCTRL_8") (pintype "bidirectional"))
    )
    (net (code "133") (name "Net-(U7-VDD)") (class "Default")
      (node (ref "C11") (pin "P$1") (pinfunction "P$1_P$1") (pintype "bidirectional"))
      (node (ref "C43") (pin "P$1") (pinfunction "P$1_P$1") (pintype "bidirectional"))
      (node (ref "RZ4") (pin "2") (pinfunction "2_2") (pintype "passive"))
      (node (ref "U7") (pin "1") (pinfunction "VDD_1") (pintype "bidirectional"))
    )
    (net (code "134") (name "RF1") (class "Default")
      (node (ref "A1") (pin "FEED") (pinfunction "ANTENNA_FEED") (pintype "bidirectional"))
      (node (ref "S2") (pin "9") (pinfunction "J2_9") (pintype "bidirectional"))
    )
    (net (code "135") (name "RF2") (class "Default")
      (node (ref "A2") (pin "FEED") (pinfunction "ANTENNA_FEED") (pintype "bidirectional"))
      (node (ref "S2") (pin "3") (pinfunction "J3_3") (pintype "bidirectional"))
    )
    (net (code "136") (name "RF3") (class "Default")
      (node (ref "A3") (pin "FEED") (pinfunction "ANTENNA_FEED") (pintype "bidirectional"))
      (node (ref "S2") (pin "1") (pinfunction "J1_1") (pintype "bidirectional"))
    )
    (net (code "137") (name "RFC") (class "Default")
      (node (ref "S2") (pin "11") (pinfunction "RFC_11") (pintype "bidirectional"))
      (node (ref "U7") (pin "2") (pinfunction "LNA_IN_2") (pintype "bidirectional"))
    )
    (net (code "138") (name "VBAT") (class "Default")
      (node (ref "C42") (pin "1") (pinfunction "1_1") (pintype "bidirectional"))
      (node (ref "J3") (pin "1") (pinfunction "1_1") (pintype "passive"))
      (node (ref "J4") (pin "3") (pinfunction "3_3") (pintype "bidirectional"))
      (node (ref "J4") (pin "3SUPP") (pinfunction "3_3SUPP") (pintype "bidirectional"))
      (node (ref "S1") (pin "2") (pinfunction "2_2") (pintype "passive"))
      (node (ref "U3") (pin "10") (pinfunction "OUT_10") (pintype "bidirectional"))
    )
    (net (code "139") (name "VBAT_SWITCHED") (class "Default")
      (node (ref "C45") (pin "2") (pinfunction "2_2") (pintype "bidirectional"))
      (node (ref "C48") (pin "1") (pinfunction "1_1") (pintype "bidirectional"))
      (node (ref "C51") (pin "P$1") (pinfunction "1_P$1") (pintype "bidirectional"))
      (node (ref "C68") (pin "P$1") (pinfunction "1_P$1") (pintype "bidirectional"))
      (node (ref "R28") (pin "2") (pinfunction "2_2") (pintype "passive"))
      (node (ref "R29") (pin "1") (pinfunction "1_1") (pintype "passive"))
      (node (ref "R30") (pin "1") (pinfunction "1_1") (pintype "passive"))
      (node (ref "S1") (pin "3") (pinfunction "3_3") (pintype "passive"))
      (node (ref "VR1") (pin "1") (pinfunction "VIN2_1") (pintype "bidirectional"))
      (node (ref "VR1") (pin "7") (pinfunction "VIN1_7") (pintype "bidirectional"))
      (node (ref "VR4") (pin "4") (pinfunction "IN_4") (pintype "bidirectional"))
      (node (ref "VR5") (pin "1") (pinfunction "IN_1") (pintype "bidirectional"))
    )
    (net (code "140") (name "VDDAUDA_1P8-CLEAN") (class "Default")
      (node (ref "C72") (pin "P$1") (pinfunction "1_P$1") (pintype "bidirectional"))
      (node (ref "C78") (pin "P$1") (pinfunction "1_P$1") (pintype "bidirectional"))
      (node (ref "U1") (pin "B11") (pinfunction "VDDAUDA_B11") (pintype "bidirectional"))
      (node (ref "VR2") (pin "1") (pinfunction "OUT_1") (pintype "power_in"))
    )
    (net (code "141") (name "VQI") (class "Default")
      (node (ref "C29") (pin "1") (pinfunction "1_1") (pintype "bidirectional"))
      (node (ref "C41") (pin "1") (pinfunction "1_1") (pintype "bidirectional"))
      (node (ref "C53") (pin "1") (pinfunction "1_1") (pintype "bidirectional"))
      (node (ref "Q1") (pin "A2") (pinfunction "D1_A2") (pintype "bidirectional"))
      (node (ref "Q1") (pin "A3") (pinfunction "D1_A3") (pintype "bidirectional"))
      (node (ref "Q1") (pin "B3") (pinfunction "D1_B3") (pintype "bidirectional"))
      (node (ref "U3") (pin "1") (pinfunction "IN_1") (pintype "bidirectional"))
      (node (ref "U4") (pin "4") (pinfunction "OUT_4") (pintype "bidirectional"))
    )
    (net (code "142") (name "VR1_1P8_EN") (class "Default")
      (node (ref "R30") (pin "2") (pinfunction "2_2") (pintype "passive"))
      (node (ref "VR1") (pin "6") (pinfunction "EN1_6") (pintype "bidirectional"))
    )
    (net (code "143") (name "VR1_2P5_EN") (class "Default")
      (node (ref "R29") (pin "2") (pinfunction "2_2") (pintype "passive"))
      (node (ref "VR1") (pin "12") (pinfunction "EN2_12") (pintype "bidirectional"))
    )
    (net (code "144") (name "VUSB") (class "Default")
      (node (ref "C40") (pin "2") (pinfunction "2_2") (pintype "bidirectional"))
      (node (ref "D5") (pin "4") (pinfunction "VCC_4") (pintype "bidirectional"))
      (node (ref "J7") (pin "A4/B9") (pinfunction "VBUS_A4/B9") (pintype "power_in"))
      (node (ref "J7") (pin "B4/A9") (pinfunction "VBUS_B4/A9") (pintype "power_in"))
      (node (ref "Q1") (pin "B2") (pinfunction "D2_B2") (pintype "bidirectional"))
      (node (ref "Q1") (pin "C2") (pinfunction "D2_C2") (pintype "bidirectional"))
      (node (ref "Q1") (pin "C3") (pinfunction "D2_C3") (pintype "bidirectional"))
      (node (ref "R26") (pin "2") (pinfunction "2_2") (pintype "passive"))
      (node (ref "U4") (pin "9") (pinfunction "AD_9") (pintype "bidirectional"))
    )
    (net (code "145") (name "unconnected-(J7-SBU1-PadA8)") (class "Default")
      (node (ref "J7") (pin "A8") (pinfunction "SBU1_A8") (pintype "bidirectional"))
    )
    (net (code "146") (name "unconnected-(J7-SBU2-PadB8)") (class "Default")
      (node (ref "J7") (pin "B8") (pinfunction "SBU2_B8") (pintype "bidirectional"))
    )
    (net (code "147") (name "unconnected-(Q1-S-PadB1)") (class "Default")
      (node (ref "Q1") (pin "B1") (pinfunction "S_B1") (pintype "bidirectional"))
    )
    (net (code "148") (name "unconnected-(S1-Pad1)") (class "Default")
      (node (ref "S1") (pin "1") (pinfunction "1_1") (pintype "passive"))
    )
    (net (code "149") (name "unconnected-(U1-GPIO0-PadH3)") (class "Default")
      (node (ref "U1") (pin "H3") (pinfunction "GPIO0_H3") (pintype "bidirectional"))
    )
    (net (code "150") (name "unconnected-(U1-GPIO1-PadJ4)") (class "Default")
      (node (ref "U1") (pin "J4") (pinfunction "GPIO1_J4") (pintype "bidirectional"))
    )
    (net (code "151") (name "unconnected-(U1-GPIO2-PadK4)") (class "Default")
      (node (ref "U1") (pin "K4") (pinfunction "GPIO2_K4") (pintype "bidirectional"))
    )
    (net (code "152") (name "unconnected-(U1-GPIO4-PadM4)") (class "Default")
      (node (ref "U1") (pin "M4") (pinfunction "GPIO4_M4") (pintype "bidirectional"))
    )
    (net (code "153") (name "unconnected-(U1-GPIO5-PadH4)") (class "Default")
      (node (ref "U1") (pin "H4") (pinfunction "GPIO5_H4") (pintype "bidirectional"))
    )
    (net (code "154") (name "unconnected-(U1-GPIO7-PadJ6)") (class "Default")
      (node (ref "U1") (pin "J6") (pinfunction "GPIO7_J6") (pintype "bidirectional"))
    )
    (net (code "155") (name "unconnected-(U1-GPIO11-PadE4)") (class "Default")
      (node (ref "U1") (pin "E4") (pinfunction "GPIO11_E4") (pintype "bidirectional"))
    )
    (net (code "156") (name "unconnected-(U1-GPIO12-PadB4)") (class "Default")
      (node (ref "U1") (pin "B4") (pinfunction "GPIO12_B4") (pintype "bidirectional"))
    )
    (net (code "157") (name "unconnected-(U1-GPIO15-PadE5)") (class "Default")
      (node (ref "U1") (pin "E5") (pinfunction "GPIO15_E5") (pintype "bidirectional"))
    )
    (net (code "158") (name "unconnected-(U1-GPIO16-PadD7)") (class "Default")
      (node (ref "U1") (pin "D7") (pinfunction "GPIO16_D7") (pintype "bidirectional"))
    )
    (net (code "159") (name "unconnected-(U1-GPIO19-PadC3)") (class "Default")
      (node (ref "U1") (pin "C3") (pinfunction "GPIO19_C3") (pintype "bidirectional"))
    )
    (net (code "160") (name "unconnected-(U1-GPIO22-PadF3)") (class "Default")
      (node (ref "U1") (pin "F3") (pinfunction "GPIO22_F3") (pintype "bidirectional"))
    )
    (net (code "161") (name "unconnected-(U1-GPIO23-PadF2)") (class "Default")
      (node (ref "U1") (pin "F2") (pinfunction "GPIO23_F2") (pintype "bidirectional"))
    )
    (net (code "162") (name "unconnected-(U1-GPIO28-PadE3)") (class "Default")
      (node (ref "U1") (pin "E3") (pinfunction "GPIO28_E3") (pintype "bidirectional"))
    )
    (net (code "163") (name "unconnected-(U1-GPIO29-PadF4)") (class "Default")
      (node (ref "U1") (pin "F4") (pinfunction "GPIO29_F4") (pintype "bidirectional"))
    )
    (net (code "164") (name "unconnected-(U1-GPIO37-PadF11)") (class "Default")
      (node (ref "U1") (pin "F11") (pinfunction "GPIO37_F11") (pintype "bidirectional"))
    )
    (net (code "165") (name "unconnected-(U1-GPIO38-PadF12)") (class "Default")
      (node (ref "U1") (pin "F12") (pinfunction "GPIO38_F12") (pintype "bidirectional"))
    )
    (net (code "166") (name "unconnected-(U1-GPIO52-PadC10)") (class "Default")
      (node (ref "U1") (pin "C10") (pinfunction "GPIO52_C10") (pintype "bidirectional"))
    )
    (net (code "167") (name "unconnected-(U1-GPIO54-PadD10)") (class "Default")
      (node (ref "U1") (pin "D10") (pinfunction "GPIO54_D10") (pintype "bidirectional"))
    )
    (net (code "168") (name "unconnected-(U1-GPIO56-PadE10)") (class "Default")
      (node (ref "U1") (pin "E10") (pinfunction "GPIO56_E10") (pintype "bidirectional"))
    )
    (net (code "169") (name "unconnected-(U1-GPIO57-PadE9)") (class "Default")
      (node (ref "U1") (pin "E9") (pinfunction "GPIO57_E9") (pintype "bidirectional"))
    )
    (net (code "170") (name "unconnected-(U1-GPIO59-PadJ8)") (class "Default")
      (node (ref "U1") (pin "J8") (pinfunction "GPIO59_J8") (pintype "bidirectional"))
    )
    (net (code "171") (name "unconnected-(U1-GPIO61-PadK6)") (class "Default")
      (node (ref "U1") (pin "K6") (pinfunction "GPIO61_K6") (pintype "bidirectional"))
    )
    (net (code "172") (name "unconnected-(U1-GPIO62-PadL6)") (class "Default")
      (node (ref "U1") (pin "L6") (pinfunction "GPIO62_L6") (pintype "bidirectional"))
    )
    (net (code "173") (name "unconnected-(U1-GPIO64-PadB6)") (class "Default")
      (node (ref "U1") (pin "B6") (pinfunction "GPIO64_B6") (pintype "bidirectional"))
    )
    (net (code "174") (name "unconnected-(U1-GPIO67-PadC6)") (class "Default")
      (node (ref "U1") (pin "C6") (pinfunction "GPIO67_C6") (pintype "bidirectional"))
    )
    (net (code "175") (name "unconnected-(U1-GPIO68-PadB7)") (class "Default")
      (node (ref "U1") (pin "B7") (pinfunction "GPIO68_B7") (pintype "bidirectional"))
    )
    (net (code "176") (name "unconnected-(U1-GPIO70-PadC5)") (class "Default")
      (node (ref "U1") (pin "C5") (pinfunction "GPIO70_C5") (pintype "bidirectional"))
    )
    (net (code "177") (name "unconnected-(U1-GPIO71-PadC7)") (class "Default")
      (node (ref "U1") (pin "C7") (pinfunction "GPIO71_C7") (pintype "bidirectional"))
    )
    (net (code "178") (name "unconnected-(U1-GPIO73-PadD8)") (class "Default")
      (node (ref "U1") (pin "D8") (pinfunction "GPIO73_D8") (pintype "bidirectional"))
    )
    (net (code "179") (name "unconnected-(U1-GPIO74-PadG11)") (class "Default")
      (node (ref "U1") (pin "G11") (pinfunction "GPIO74_G11") (pintype "bidirectional"))
    )
    (net (code "180") (name "unconnected-(U1-GPIO75-PadH11)") (class "Default")
      (node (ref "U1") (pin "H11") (pinfunction "GPIO75_H11") (pintype "bidirectional"))
    )
    (net (code "181") (name "unconnected-(U1-GPIO76-PadJ11)") (class "Default")
      (node (ref "U1") (pin "J11") (pinfunction "GPIO76_J11") (pintype "bidirectional"))
    )
    (net (code "182") (name "unconnected-(U1-GPIO77-PadK11)") (class "Default")
      (node (ref "U1") (pin "K11") (pinfunction "GPIO77_K11") (pintype "bidirectional"))
    )
    (net (code "183") (name "unconnected-(U1-GPIO82-PadL9)") (class "Default")
      (node (ref "U1") (pin "L9") (pinfunction "GPIO82_L9") (pintype "bidirectional"))
    )
    (net (code "184") (name "unconnected-(U1-GPIO83-PadK9)") (class "Default")
      (node (ref "U1") (pin "K9") (pinfunction "GPIO83_K9") (pintype "bidirectional"))
    )
    (net (code "185") (name "unconnected-(U1-GPIO84-PadJ9)") (class "Default")
      (node (ref "U1") (pin "J9") (pinfunction "GPIO84_J9") (pintype "bidirectional"))
    )
    (net (code "186") (name "unconnected-(U1-GPIO85-PadH9)") (class "Default")
      (node (ref "U1") (pin "H9") (pinfunction "GPIO85_H9") (pintype "bidirectional"))
    )
    (net (code "187") (name "unconnected-(U1-GPIO86-PadG10)") (class "Default")
      (node (ref "U1") (pin "G10") (pinfunction "GPIO86_G10") (pintype "bidirectional"))
    )
    (net (code "188") (name "unconnected-(U1-GPIO87-PadG9)") (class "Default")
      (node (ref "U1") (pin "G9") (pinfunction "GPIO87_G9") (pintype "bidirectional"))
    )
    (net (code "189") (name "unconnected-(U1-GPIO89-PadF10)") (class "Default")
      (node (ref "U1") (pin "F10") (pinfunction "GPIO89_F10") (pintype "bidirectional"))
    )
    (net (code "190") (name "unconnected-(U1-GPIO90-PadJ2)") (class "Default")
      (node (ref "U1") (pin "J2") (pinfunction "GPIO90_J2") (pintype "bidirectional"))
    )
    (net (code "191") (name "unconnected-(U1-GPIO91-PadK2)") (class "Default")
      (node (ref "U1") (pin "K2") (pinfunction "GPIO91_K2") (pintype "bidirectional"))
    )
    (net (code "192") (name "unconnected-(U1-LPADC_D0NSE0-PadA10)") (class "Default")
      (node (ref "U1") (pin "A10") (pinfunction "LPADC_D0NSE0_A10") (pintype "input"))
    )
    (net (code "193") (name "unconnected-(U1-LPADC_D0PSE1-PadA11)") (class "Default")
      (node (ref "U1") (pin "A11") (pinfunction "LPADC_D0PSE1_A11") (pintype "input"))
    )
    (net (code "194") (name "unconnected-(U1-LPADC_D1NSE2-PadC11)") (class "Default")
      (node (ref "U1") (pin "C11") (pinfunction "LPADC_D1NSE2_C11") (pintype "input"))
    )
    (net (code "195") (name "unconnected-(U1-LPADC_D1PSE3-PadD11)") (class "Default")
      (node (ref "U1") (pin "D11") (pinfunction "LPADC_D1PSE3_D11") (pintype "input"))
    )
    (net (code "196") (name "unconnected-(U1-MIPI_CLKN-PadJ12)") (class "Default")
      (node (ref "U1") (pin "J12") (pinfunction "MIPI_CLKN_J12") (pintype "bidirectional"))
    )
    (net (code "197") (name "unconnected-(U1-MIPI_CLKP-PadK12)") (class "Default")
      (node (ref "U1") (pin "K12") (pinfunction "MIPI_CLKP_K12") (pintype "bidirectional"))
    )
    (net (code "198") (name "unconnected-(U1-MIPI_DON-PadL12)") (class "Default")
      (node (ref "U1") (pin "L12") (pinfunction "MIPI_DON_L12") (pintype "bidirectional"))
    )
    (net (code "199") (name "unconnected-(U1-MIPI_DOP-PadM12)") (class "Default")
      (node (ref "U1") (pin "M12") (pinfunction "MIPI_DOP_M12") (pintype "bidirectional"))
    )
    (net (code "200") (name "unconnected-(U1-TXEN-PadK1)") (class "Default")
      (node (ref "U1") (pin "K1") (pinfunction "TXEN_K1") (pintype "output"))
    )
    (net (code "201") (name "unconnected-(VR1-NC1-Pad5)") (class "Default")
      (node (ref "VR1") (pin "5") (pinfunction "NC1_5") (pintype "bidirectional"))
    )
    (net (code "202") (name "unconnected-(VR1-NC2-Pad11)") (class "Default")
      (node (ref "VR1") (pin "11") (pinfunction "NC2_11") (pintype "bidirectional"))
    )
    (net (code "203") (name "~{AD_EN}") (class "Default")
      (node (ref "Q1") (pin "A1") (pinfunction "G1_A1") (pintype "input"))
      (node (ref "Q1") (pin "C1") (pinfunction "G2_C1") (pintype "input"))
      (node (ref "U4") (pin "8") (pinfunction "~{AD-EN}_8") (pintype "bidirectional"))
    )
  )
)
